# EP3C25.net
KiCad netlist of a schematic drawn in Altium Designer
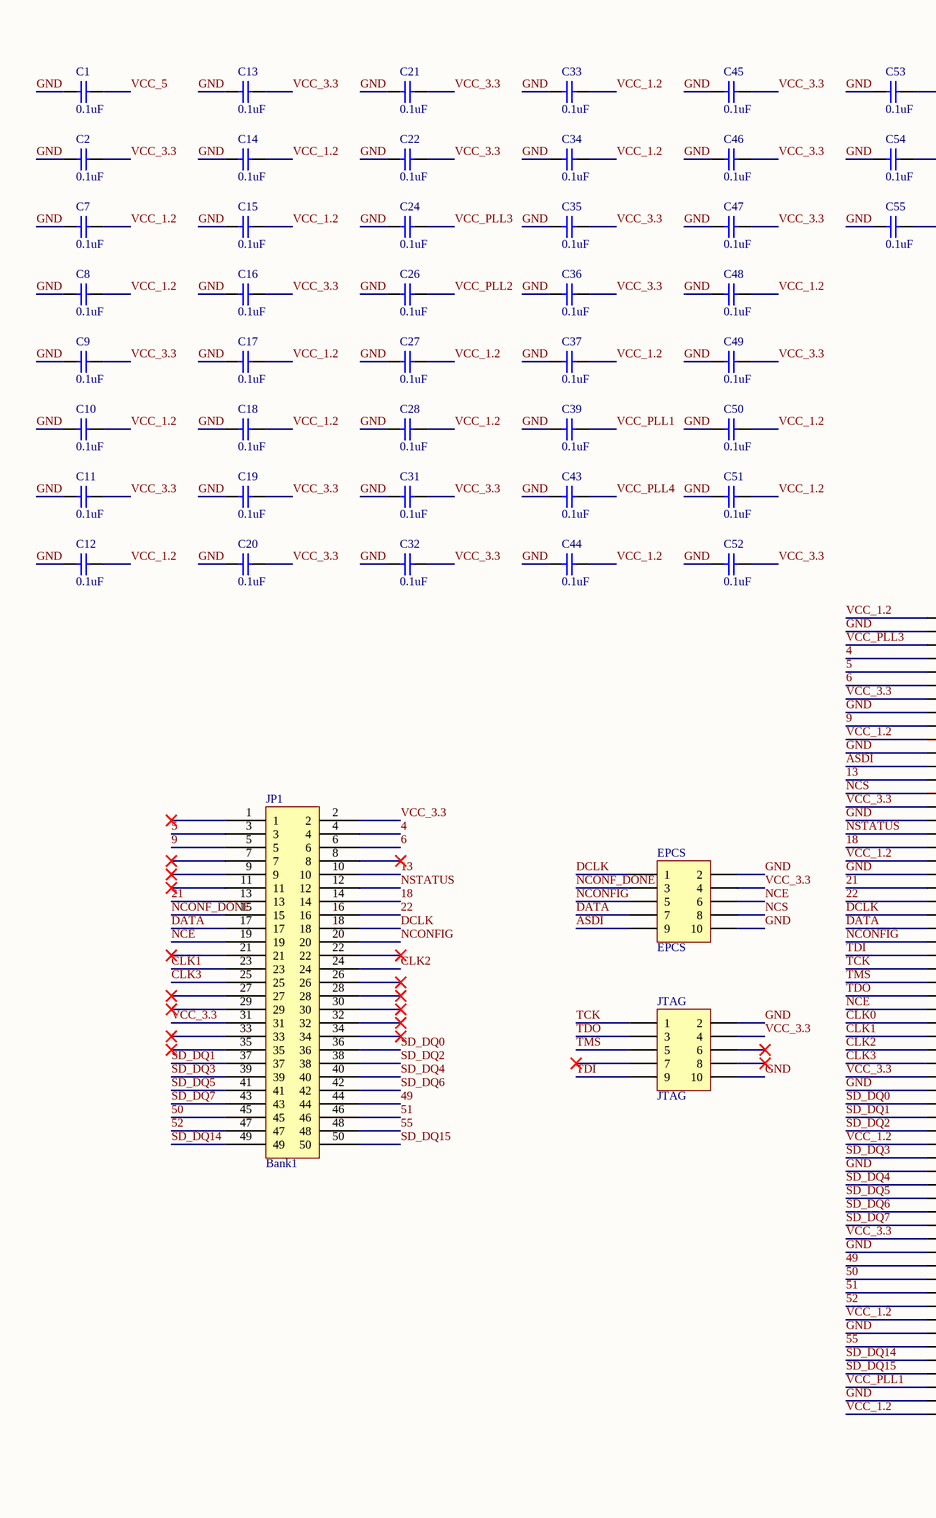
[diagram p0: EP3C25.SchDoc, left]
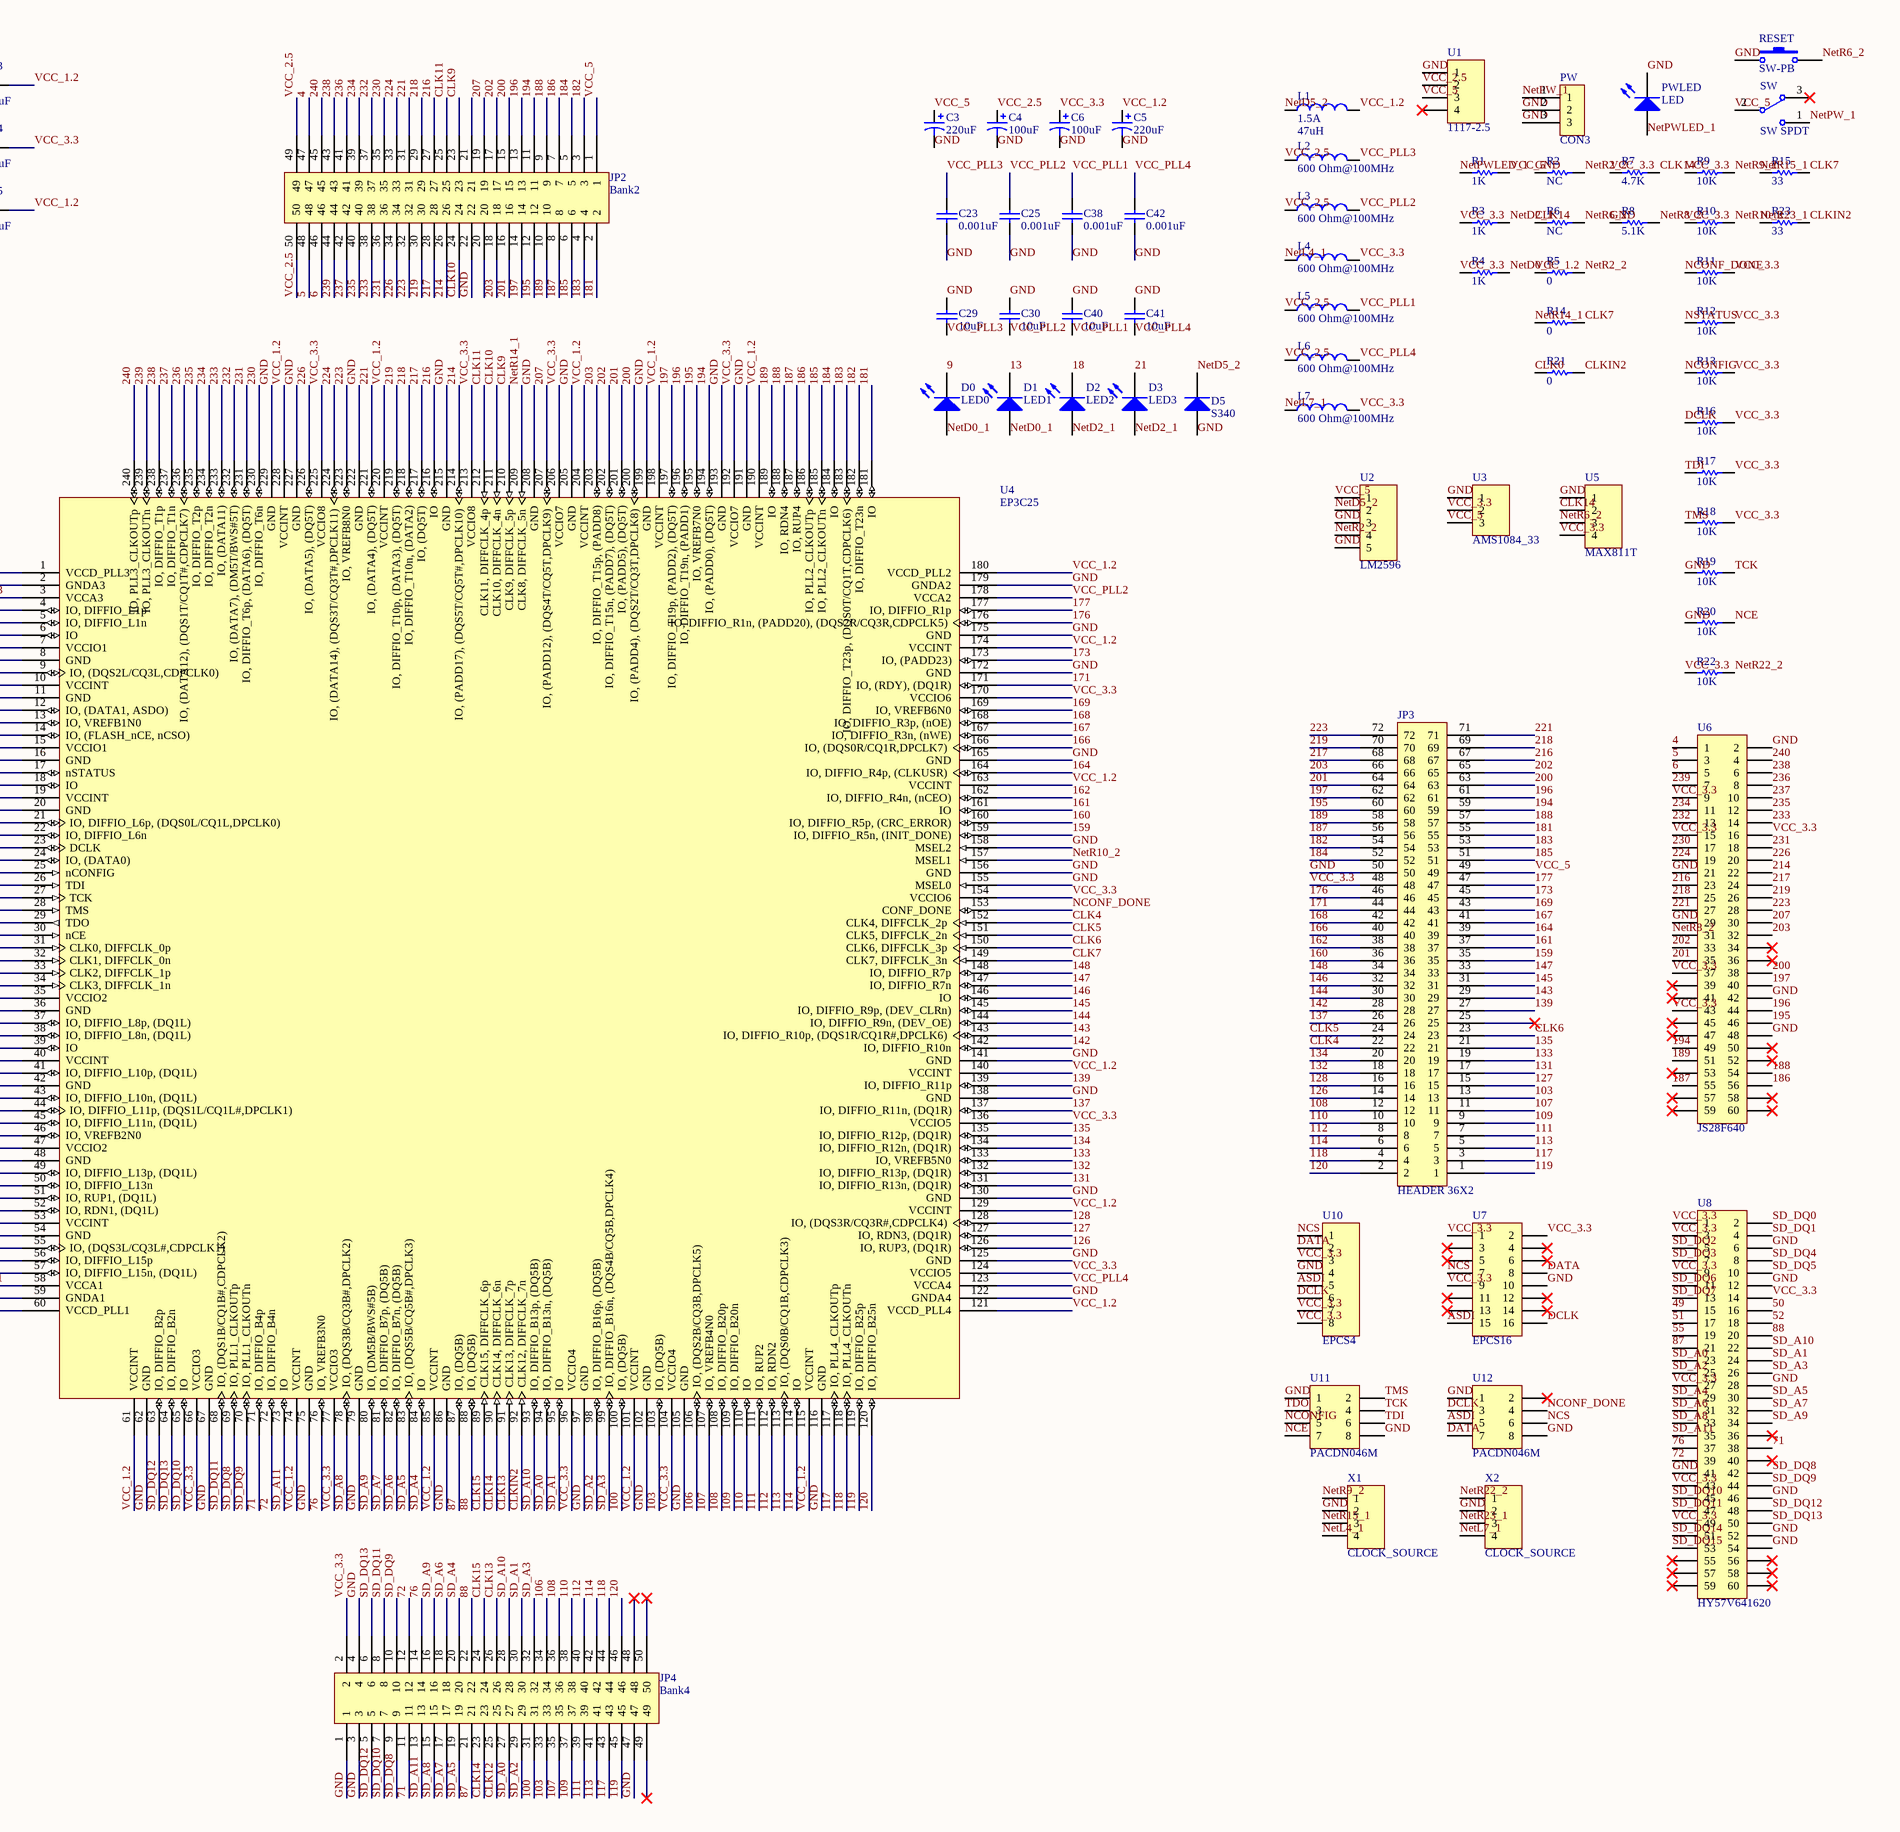
[diagram p1: EP3C25.SchDoc, right]

(export (version "E")
  (design (tool "Eeschema 10.0.6"))
  (components
    (comp (ref "C1")
      (value "0.1uF")
      (footprint "0805C")
      (description "Capacitor")
      (fields (field (name "PUBLISHER") "Altium Limited"))
      (libsource (lib "Miscellaneous Devices") (part "Cap"))
    )
    (comp (ref "C2")
      (value "0.1uF")
      (footprint "0805C")
      (description "Capacitor")
      (fields (field (name "PUBLISHER") "Altium Limited"))
      (libsource (lib "Miscellaneous Devices") (part "Cap"))
    )
    (comp (ref "C3")
      (value "220uF")
      (footprint "Cap6.6*6.6")
      (description "Polarized Capacitor (Radial)")
      (fields (field (name "PUBLISHER") "Altium Limited"))
      (libsource (lib "Miscellaneous Devices") (part "Cap Pol1"))
    )
    (comp (ref "C4")
      (value "100uF")
      (footprint "Cap6.6*6.6")
      (description "Polarized Capacitor (Radial)")
      (fields (field (name "PUBLISHER") "Altium Limited"))
      (libsource (lib "Miscellaneous Devices") (part "Cap Pol1"))
    )
    (comp (ref "C5")
      (value "220uF")
      (footprint "8228")
      (description "Polarized Capacitor (Radial)")
      (fields (field (name "PUBLISHER") "Altium Limited"))
      (libsource (lib "Miscellaneous Devices") (part "Cap Pol1"))
    )
    (comp (ref "C6")
      (value "100uF")
      (footprint "Cap6.6*6.6")
      (description "Polarized Capacitor (Radial)")
      (fields (field (name "PUBLISHER") "Altium Limited"))
      (libsource (lib "Miscellaneous Devices") (part "Cap Pol1"))
    )
    (comp (ref "C7")
      (value "0.1uF")
      (footprint "0805C")
      (description "Capacitor")
      (fields (field (name "PUBLISHER") "Altium Limited"))
      (libsource (lib "Miscellaneous Devices") (part "Cap"))
    )
    (comp (ref "C8")
      (value "0.1uF")
      (footprint "0805C")
      (description "Capacitor")
      (fields (field (name "PUBLISHER") "Altium Limited"))
      (libsource (lib "Miscellaneous Devices") (part "Cap"))
    )
    (comp (ref "C9")
      (value "0.1uF")
      (footprint "0805C")
      (description "Capacitor")
      (fields (field (name "PUBLISHER") "Altium Limited"))
      (libsource (lib "Miscellaneous Devices") (part "Cap"))
    )
    (comp (ref "C10")
      (value "0.1uF")
      (footprint "0805C")
      (description "Capacitor")
      (fields (field (name "PUBLISHER") "Altium Limited"))
      (libsource (lib "Miscellaneous Devices") (part "Cap"))
    )
    (comp (ref "C11")
      (value "0.1uF")
      (footprint "0805C")
      (description "Capacitor")
      (fields (field (name "PUBLISHER") "Altium Limited"))
      (libsource (lib "Miscellaneous Devices") (part "Cap"))
    )
    (comp (ref "C12")
      (value "0.1uF")
      (footprint "0805C")
      (description "Capacitor")
      (fields (field (name "PUBLISHER") "Altium Limited"))
      (libsource (lib "Miscellaneous Devices") (part "Cap"))
    )
    (comp (ref "C13")
      (value "0.1uF")
      (footprint "0805C")
      (description "Capacitor")
      (fields (field (name "PUBLISHER") "Altium Limited"))
      (libsource (lib "Miscellaneous Devices") (part "Cap"))
    )
    (comp (ref "C14")
      (value "0.1uF")
      (footprint "0805C")
      (description "Capacitor")
      (fields (field (name "PUBLISHER") "Altium Limited"))
      (libsource (lib "Miscellaneous Devices") (part "Cap"))
    )
    (comp (ref "C15")
      (value "0.1uF")
      (footprint "0805C")
      (description "Capacitor")
      (fields (field (name "PUBLISHER") "Altium Limited"))
      (libsource (lib "Miscellaneous Devices") (part "Cap"))
    )
    (comp (ref "C16")
      (value "0.1uF")
      (footprint "0805C")
      (description "Capacitor")
      (fields (field (name "PUBLISHER") "Altium Limited"))
      (libsource (lib "Miscellaneous Devices") (part "Cap"))
    )
    (comp (ref "C17")
      (value "0.1uF")
      (footprint "0805C")
      (description "Capacitor")
      (fields (field (name "PUBLISHER") "Altium Limited"))
      (libsource (lib "Miscellaneous Devices") (part "Cap"))
    )
    (comp (ref "C18")
      (value "0.1uF")
      (footprint "0805C")
      (description "Capacitor")
      (fields (field (name "PUBLISHER") "Altium Limited"))
      (libsource (lib "Miscellaneous Devices") (part "Cap"))
    )
    (comp (ref "C19")
      (value "0.1uF")
      (footprint "0805C")
      (description "Capacitor")
      (fields (field (name "PUBLISHER") "Altium Limited"))
      (libsource (lib "Miscellaneous Devices") (part "Cap"))
    )
    (comp (ref "C20")
      (value "0.1uF")
      (footprint "0805C")
      (description "Capacitor")
      (fields (field (name "PUBLISHER") "Altium Limited"))
      (libsource (lib "Miscellaneous Devices") (part "Cap"))
    )
    (comp (ref "C21")
      (value "0.1uF")
      (footprint "0805C")
      (description "Capacitor")
      (fields (field (name "PUBLISHER") "Altium Limited"))
      (libsource (lib "Miscellaneous Devices") (part "Cap"))
    )
    (comp (ref "C22")
      (value "0.1uF")
      (footprint "0805C")
      (description "Capacitor")
      (fields (field (name "PUBLISHER") "Altium Limited"))
      (libsource (lib "Miscellaneous Devices") (part "Cap"))
    )
    (comp (ref "C23")
      (value "0.001uF")
      (footprint "0805C")
      (description "Capacitor")
      (fields (field (name "PUBLISHER") "Altium Limited"))
      (libsource (lib "Miscellaneous Devices") (part "Cap"))
    )
    (comp (ref "C24")
      (value "0.1uF")
      (footprint "0805C")
      (description "Capacitor")
      (fields (field (name "PUBLISHER") "Altium Limited"))
      (libsource (lib "Miscellaneous Devices") (part "Cap"))
    )
    (comp (ref "C25")
      (value "0.001uF")
      (footprint "0805C")
      (description "Capacitor")
      (fields (field (name "PUBLISHER") "Altium Limited"))
      (libsource (lib "Miscellaneous Devices") (part "Cap"))
    )
    (comp (ref "C26")
      (value "0.1uF")
      (footprint "0805C")
      (description "Capacitor")
      (fields (field (name "PUBLISHER") "Altium Limited"))
      (libsource (lib "Miscellaneous Devices") (part "Cap"))
    )
    (comp (ref "C27")
      (value "0.1uF")
      (footprint "0805C")
      (description "Capacitor")
      (fields (field (name "PUBLISHER") "Altium Limited"))
      (libsource (lib "Miscellaneous Devices") (part "Cap"))
    )
    (comp (ref "C28")
      (value "0.1uF")
      (footprint "0805C")
      (description "Capacitor")
      (fields (field (name "PUBLISHER") "Altium Limited"))
      (libsource (lib "Miscellaneous Devices") (part "Cap"))
    )
    (comp (ref "C29")
      (value "10uF")
      (footprint "3216C/A")
      (description "Capacitor")
      (fields (field (name "PUBLISHER") "Altium Limited"))
      (libsource (lib "Miscellaneous Devices") (part "Cap"))
    )
    (comp (ref "C30")
      (value "10uF")
      (footprint "3216C/A")
      (description "Capacitor")
      (fields (field (name "PUBLISHER") "Altium Limited"))
      (libsource (lib "Miscellaneous Devices") (part "Cap"))
    )
    (comp (ref "C31")
      (value "0.1uF")
      (footprint "0805C")
      (description "Capacitor")
      (fields (field (name "PUBLISHER") "Altium Limited"))
      (libsource (lib "Miscellaneous Devices") (part "Cap"))
    )
    (comp (ref "C32")
      (value "0.1uF")
      (footprint "0805C")
      (description "Capacitor")
      (fields (field (name "PUBLISHER") "Altium Limited"))
      (libsource (lib "Miscellaneous Devices") (part "Cap"))
    )
    (comp (ref "C33")
      (value "0.1uF")
      (footprint "0805C")
      (description "Capacitor")
      (fields (field (name "PUBLISHER") "Altium Limited"))
      (libsource (lib "Miscellaneous Devices") (part "Cap"))
    )
    (comp (ref "C34")
      (value "0.1uF")
      (footprint "0805C")
      (description "Capacitor")
      (fields (field (name "PUBLISHER") "Altium Limited"))
      (libsource (lib "Miscellaneous Devices") (part "Cap"))
    )
    (comp (ref "C35")
      (value "0.1uF")
      (footprint "0805C")
      (description "Capacitor")
      (fields (field (name "PUBLISHER") "Altium Limited"))
      (libsource (lib "Miscellaneous Devices") (part "Cap"))
    )
    (comp (ref "C36")
      (value "0.1uF")
      (footprint "0805C")
      (description "Capacitor")
      (fields (field (name "PUBLISHER") "Altium Limited"))
      (libsource (lib "Miscellaneous Devices") (part "Cap"))
    )
    (comp (ref "C37")
      (value "0.1uF")
      (footprint "0805C")
      (description "Capacitor")
      (fields (field (name "PUBLISHER") "Altium Limited"))
      (libsource (lib "Miscellaneous Devices") (part "Cap"))
    )
    (comp (ref "C38")
      (value "0.001uF")
      (footprint "0805C")
      (description "Capacitor")
      (fields (field (name "PUBLISHER") "Altium Limited"))
      (libsource (lib "Miscellaneous Devices") (part "Cap"))
    )
    (comp (ref "C39")
      (value "0.1uF")
      (footprint "0805C")
      (description "Capacitor")
      (fields (field (name "PUBLISHER") "Altium Limited"))
      (libsource (lib "Miscellaneous Devices") (part "Cap"))
    )
    (comp (ref "C40")
      (value "10uF")
      (footprint "3216C/A")
      (description "Capacitor")
      (fields (field (name "PUBLISHER") "Altium Limited"))
      (libsource (lib "Miscellaneous Devices") (part "Cap"))
    )
    (comp (ref "C41")
      (value "10uF")
      (footprint "3216C/A")
      (description "Capacitor")
      (fields (field (name "PUBLISHER") "Altium Limited"))
      (libsource (lib "Miscellaneous Devices") (part "Cap"))
    )
    (comp (ref "C42")
      (value "0.001uF")
      (footprint "0805C")
      (description "Capacitor")
      (fields (field (name "PUBLISHER") "Altium Limited"))
      (libsource (lib "Miscellaneous Devices") (part "Cap"))
    )
    (comp (ref "C43")
      (value "0.1uF")
      (footprint "0805C")
      (description "Capacitor")
      (fields (field (name "PUBLISHER") "Altium Limited"))
      (libsource (lib "Miscellaneous Devices") (part "Cap"))
    )
    (comp (ref "C44")
      (value "0.1uF")
      (footprint "0805C")
      (description "Capacitor")
      (fields (field (name "PUBLISHER") "Altium Limited"))
      (libsource (lib "Miscellaneous Devices") (part "Cap"))
    )
    (comp (ref "C45")
      (value "0.1uF")
      (footprint "0805C")
      (description "Capacitor")
      (fields (field (name "PUBLISHER") "Altium Limited"))
      (libsource (lib "Miscellaneous Devices") (part "Cap"))
    )
    (comp (ref "C46")
      (value "0.1uF")
      (footprint "0805C")
      (description "Capacitor")
      (fields (field (name "PUBLISHER") "Altium Limited"))
      (libsource (lib "Miscellaneous Devices") (part "Cap"))
    )
    (comp (ref "C47")
      (value "0.1uF")
      (footprint "0805C")
      (description "Capacitor")
      (fields (field (name "PUBLISHER") "Altium Limited"))
      (libsource (lib "Miscellaneous Devices") (part "Cap"))
    )
    (comp (ref "C48")
      (value "0.1uF")
      (footprint "0805C")
      (description "Capacitor")
      (fields (field (name "PUBLISHER") "Altium Limited"))
      (libsource (lib "Miscellaneous Devices") (part "Cap"))
    )
    (comp (ref "C49")
      (value "0.1uF")
      (footprint "0805C")
      (description "Capacitor")
      (fields (field (name "PUBLISHER") "Altium Limited"))
      (libsource (lib "Miscellaneous Devices") (part "Cap"))
    )
    (comp (ref "C50")
      (value "0.1uF")
      (footprint "0805C")
      (description "Capacitor")
      (fields (field (name "PUBLISHER") "Altium Limited"))
      (libsource (lib "Miscellaneous Devices") (part "Cap"))
    )
    (comp (ref "C51")
      (value "0.1uF")
      (footprint "0805C")
      (description "Capacitor")
      (fields (field (name "PUBLISHER") "Altium Limited"))
      (libsource (lib "Miscellaneous Devices") (part "Cap"))
    )
    (comp (ref "C52")
      (value "0.1uF")
      (footprint "0805C")
      (description "Capacitor")
      (fields (field (name "PUBLISHER") "Altium Limited"))
      (libsource (lib "Miscellaneous Devices") (part "Cap"))
    )
    (comp (ref "C53")
      (value "0.1uF")
      (footprint "0805C")
      (description "Capacitor")
      (fields (field (name "PUBLISHER") "Altium Limited"))
      (libsource (lib "Miscellaneous Devices") (part "Cap"))
    )
    (comp (ref "C54")
      (value "0.1uF")
      (footprint "0805C")
      (description "Capacitor")
      (fields (field (name "PUBLISHER") "Altium Limited"))
      (libsource (lib "Miscellaneous Devices") (part "Cap"))
    )
    (comp (ref "C55")
      (value "0.1uF")
      (footprint "0805C")
      (description "Capacitor")
      (fields (field (name "PUBLISHER") "Altium Limited"))
      (libsource (lib "Miscellaneous Devices") (part "Cap"))
    )
    (comp (ref "D0")
      (value "LED0")
      (footprint "0805A")
      (description "Typical INFRARED GaAs LED")
      (fields (field (name "PUBLISHER") "Altium Limited"))
      (libsource (lib "Miscellaneous Devices") (part "LED0"))
    )
    (comp (ref "D1")
      (value "LED1")
      (footprint "0805A")
      (description "Typical INFRARED GaAs LED")
      (fields (field (name "PUBLISHER") "Altium Limited"))
      (libsource (lib "Miscellaneous Devices") (part "LED0"))
    )
    (comp (ref "D2")
      (value "LED2")
      (footprint "0805A")
      (description "Typical INFRARED GaAs LED")
      (fields (field (name "PUBLISHER") "Altium Limited"))
      (libsource (lib "Miscellaneous Devices") (part "LED0"))
    )
    (comp (ref "D3")
      (value "LED3")
      (footprint "0805A")
      (description "Typical INFRARED GaAs LED")
      (fields (field (name "PUBLISHER") "Altium Limited"))
      (libsource (lib "Miscellaneous Devices") (part "LED0"))
    )
    (comp (ref "D5")
      (value "S340")
      (footprint "SMB")
      (description "Default Diode")
      (fields (field (name "PUBLISHER") "Altium Limited"))
      (libsource (lib "Miscellaneous Devices") (part "Diode"))
    )
    (comp (ref "EPCS")
      (value "EPCS")
      (footprint "IDC10_S")
      (description "Header, 5-Pin, Dual row")
      (fields (field (name "PUBLISHER") "Altium Limited"))
      (libsource (lib "Miscellaneous Connectors") (part "Header 5X2"))
    )
    (comp (ref "JP1")
      (value "Bank1")
      (footprint "IDC50-S")
      (libsource (lib "EP3C25") (part "CORE_CONNECTOR_LEFT"))
    )
    (comp (ref "JP2")
      (value "Bank2")
      (footprint "IDC50-S")
      (libsource (lib "EP3C25") (part "CORE_CONNECTOR_FRONT"))
    )
    (comp (ref "JP3")
      (value "HEADER 36X2")
      (footprint "IDC72_S")
      (libsource (lib "EP3C25") (part "CORE_CONNECTOR_RIGHT"))
    )
    (comp (ref "JP4")
      (value "Bank4")
      (footprint "IDC50-S")
      (libsource (lib "EP3C25") (part "CORE_CONNECTOR_BACK"))
    )
    (comp (ref "JTAG")
      (value "JTAG")
      (footprint "IDC10_S")
      (description "Header, 5-Pin, Dual row")
      (fields (field (name "PUBLISHER") "Altium Limited"))
      (libsource (lib "Miscellaneous Connectors") (part "Header 5X2"))
    )
    (comp (ref "L1")
      (value "1.5A")
      (footprint "临时画的电感封装")
      (description "Inductor")
      (fields (field (name "ALTIUM_VALUE") "47uH") (field (name "PUBLISHER") "Altium Limited"))
      (libsource (lib "Miscellaneous Devices") (part "Inductor"))
    )
    (comp (ref "L2")
      (value "600 Ohm@100MHz")
      (footprint "0805R")
      (description "Inductor")
      (fields (field (name "PUBLISHER") "Altium Limited"))
      (libsource (lib "Miscellaneous Devices") (part "Inductor"))
    )
    (comp (ref "L3")
      (value "600 Ohm@100MHz")
      (footprint "0805R")
      (description "Inductor")
      (fields (field (name "PUBLISHER") "Altium Limited"))
      (libsource (lib "Miscellaneous Devices") (part "Inductor"))
    )
    (comp (ref "L4")
      (value "600 Ohm@100MHz")
      (footprint "0805R")
      (description "Inductor")
      (fields (field (name "PUBLISHER") "Altium Limited"))
      (libsource (lib "Miscellaneous Devices") (part "Inductor"))
    )
    (comp (ref "L5")
      (value "600 Ohm@100MHz")
      (footprint "0805R")
      (description "Inductor")
      (fields (field (name "PUBLISHER") "Altium Limited"))
      (libsource (lib "Miscellaneous Devices") (part "Inductor"))
    )
    (comp (ref "L6")
      (value "600 Ohm@100MHz")
      (footprint "0805R")
      (description "Inductor")
      (fields (field (name "PUBLISHER") "Altium Limited"))
      (libsource (lib "Miscellaneous Devices") (part "Inductor"))
    )
    (comp (ref "L7")
      (value "600 Ohm@100MHz")
      (footprint "0805R")
      (description "Inductor")
      (fields (field (name "PUBLISHER") "Altium Limited"))
      (libsource (lib "Miscellaneous Devices") (part "Inductor"))
    )
    (comp (ref "PW") (value "CON3") (footprint "PW_PORT") (libsource (lib "EP3C25") (part "CON3")))
    (comp (ref "PWLED")
      (value "LED")
      (footprint "0805A")
      (description "Typical INFRARED GaAs LED")
      (fields (field (name "PUBLISHER") "Altium Limited"))
      (libsource (lib "Miscellaneous Devices") (part "LED0"))
    )
    (comp (ref "R1")
      (value "1K")
      (footprint "0805R")
      (description "Resistor")
      (fields (field (name "PUBLISHER") "Altium Limited"))
      (libsource (lib "Miscellaneous Devices") (part "Res1"))
    )
    (comp (ref "R2")
      (value "NC")
      (footprint "0805R")
      (description "Resistor")
      (fields (field (name "PUBLISHER") "Altium Limited"))
      (libsource (lib "Miscellaneous Devices") (part "Res1"))
    )
    (comp (ref "R3")
      (value "1K")
      (footprint "0805R")
      (description "Resistor")
      (fields (field (name "PUBLISHER") "Altium Limited"))
      (libsource (lib "Miscellaneous Devices") (part "Res1"))
    )
    (comp (ref "R4")
      (value "1K")
      (footprint "0805R")
      (description "Resistor")
      (fields (field (name "PUBLISHER") "Altium Limited"))
      (libsource (lib "Miscellaneous Devices") (part "Res1"))
    )
    (comp (ref "R5")
      (value "0")
      (footprint "0805R")
      (description "Resistor")
      (fields (field (name "PUBLISHER") "Altium Limited"))
      (libsource (lib "Miscellaneous Devices") (part "Res1"))
    )
    (comp (ref "R6")
      (value "NC")
      (footprint "0805R")
      (description "Resistor")
      (fields (field (name "PUBLISHER") "Altium Limited"))
      (libsource (lib "Miscellaneous Devices") (part "Res1"))
    )
    (comp (ref "R7")
      (value "4.7K")
      (footprint "0805R")
      (description "Resistor")
      (fields (field (name "PUBLISHER") "Altium Limited"))
      (libsource (lib "Miscellaneous Devices") (part "Res1"))
    )
    (comp (ref "R8")
      (value "5.1K")
      (footprint "0805R")
      (description "Resistor")
      (fields (field (name "PUBLISHER") "Altium Limited"))
      (libsource (lib "Miscellaneous Devices") (part "Res1"))
    )
    (comp (ref "R9")
      (value "10K")
      (footprint "0805R")
      (description "Resistor")
      (fields (field (name "PUBLISHER") "Altium Limited"))
      (libsource (lib "Miscellaneous Devices") (part "Res1"))
    )
    (comp (ref "R10")
      (value "10K")
      (footprint "0805R")
      (description "Resistor")
      (fields (field (name "PUBLISHER") "Altium Limited"))
      (libsource (lib "Miscellaneous Devices") (part "Res1"))
    )
    (comp (ref "R11")
      (value "10K")
      (footprint "0805R")
      (description "Resistor")
      (fields (field (name "PUBLISHER") "Altium Limited"))
      (libsource (lib "Miscellaneous Devices") (part "Res1"))
    )
    (comp (ref "R12")
      (value "10K")
      (footprint "0805R")
      (description "Resistor")
      (fields (field (name "PUBLISHER") "Altium Limited"))
      (libsource (lib "Miscellaneous Devices") (part "Res1"))
    )
    (comp (ref "R13")
      (value "10K")
      (footprint "0805R")
      (description "Resistor")
      (fields (field (name "PUBLISHER") "Altium Limited"))
      (libsource (lib "Miscellaneous Devices") (part "Res1"))
    )
    (comp (ref "R14")
      (value "0")
      (footprint "0805R")
      (description "Resistor")
      (fields (field (name "PUBLISHER") "Altium Limited"))
      (libsource (lib "Miscellaneous Devices") (part "Res1"))
    )
    (comp (ref "R15")
      (value "33")
      (footprint "0805R")
      (description "Resistor")
      (fields (field (name "PUBLISHER") "Altium Limited"))
      (libsource (lib "Miscellaneous Devices") (part "Res1"))
    )
    (comp (ref "R16")
      (value "10K")
      (footprint "0805R")
      (description "Resistor")
      (fields (field (name "PUBLISHER") "Altium Limited"))
      (libsource (lib "Miscellaneous Devices") (part "Res1"))
    )
    (comp (ref "R17")
      (value "10K")
      (footprint "0805R")
      (description "Resistor")
      (fields (field (name "PUBLISHER") "Altium Limited"))
      (libsource (lib "Miscellaneous Devices") (part "Res1"))
    )
    (comp (ref "R18")
      (value "10K")
      (footprint "0805R")
      (description "Resistor")
      (fields (field (name "PUBLISHER") "Altium Limited"))
      (libsource (lib "Miscellaneous Devices") (part "Res1"))
    )
    (comp (ref "R19")
      (value "10K")
      (footprint "0805R")
      (description "Resistor")
      (fields (field (name "PUBLISHER") "Altium Limited"))
      (libsource (lib "Miscellaneous Devices") (part "Res1"))
    )
    (comp (ref "R20")
      (value "10K")
      (footprint "0805R")
      (description "Resistor")
      (fields (field (name "PUBLISHER") "Altium Limited"))
      (libsource (lib "Miscellaneous Devices") (part "Res1"))
    )
    (comp (ref "R21")
      (value "0")
      (footprint "0805R")
      (description "Resistor")
      (fields (field (name "PUBLISHER") "Altium Limited"))
      (libsource (lib "Miscellaneous Devices") (part "Res1"))
    )
    (comp (ref "R22")
      (value "10K")
      (footprint "0805R")
      (description "Resistor")
      (fields (field (name "PUBLISHER") "Altium Limited"))
      (libsource (lib "Miscellaneous Devices") (part "Res1"))
    )
    (comp (ref "R23")
      (value "33")
      (footprint "0805R")
      (description "Resistor")
      (fields (field (name "PUBLISHER") "Altium Limited"))
      (libsource (lib "Miscellaneous Devices") (part "Res1"))
    )
    (comp (ref "RESET")
      (value "SW-PB")
      (footprint "SMD_SWITH")
      (description "Switch")
      (fields (field (name "PUBLISHER") "Altium Limited"))
      (libsource (lib "Miscellaneous Devices") (part "SW-PB"))
    )
    (comp (ref "SW")
      (value "SW SPDT")
      (footprint "PW_SW")
      (description "SPDT Subminiature Toggle Switch, Right Angle Mounting, Vertical Actuation")
      (fields (field (name "PUBLISHER") "Altium Limited"))
      (libsource (lib "Miscellaneous Devices") (part "SW-SPDT"))
    )
    (comp (ref "U1")
      (value "1117-2.5")
      (footprint "SOT-223")
      (description "Header, 4-Pin")
      (fields (field (name "PUBLISHER") "Altium Limited"))
      (libsource (lib "Miscellaneous Connectors") (part "Header 4"))
    )
    (comp (ref "U2")
      (value "LM2596")
      (footprint "LM2596_TO263")
      (description "Header, 5-Pin")
      (fields (field (name "PUBLISHER") "Altium Limited"))
      (libsource (lib "Miscellaneous Connectors") (part "Header 5"))
    )
    (comp (ref "U3")
      (value "AMS1084_33")
      (footprint "AMS1084-ADJ")
      (description "Header, 3-Pin")
      (fields (field (name "PUBLISHER") "Altium Limited"))
      (libsource (lib "Miscellaneous Connectors") (part "Header 3"))
    )
    (comp (ref "U4") (value "EP3C25") (footprint "PQFP240") (libsource (lib "EP3C25") (part "EP3C25Q240C8")))
    (comp (ref "U5")
      (value "MAX811T")
      (footprint "SOT143")
      (description "Header, 4-Pin")
      (fields (field (name "PUBLISHER") "Altium Limited"))
      (libsource (lib "Miscellaneous Connectors") (part "Header 4"))
    )
    (comp (ref "U6")
      (value "JS28F640")
      (footprint "SOP56_E28F640")
      (description "Header, 30-Pin, Dual row")
      (fields (field (name "PUBLISHER") "Altium Limited"))
      (libsource (lib "Miscellaneous Connectors") (part "Header 30X2"))
    )
    (comp (ref "U7")
      (value "EPCS16")
      (footprint "SOP16_EPCS16")
      (description "Header, 8-Pin, Dual row")
      (fields (field (name "PUBLISHER") "Altium Limited"))
      (libsource (lib "Miscellaneous Connectors") (part "Header 8X2"))
    )
    (comp (ref "U8")
      (value "HY57V641620")
      (footprint "TSOP54")
      (description "Header, 30-Pin, Dual row")
      (fields (field (name "PUBLISHER") "Altium Limited"))
      (libsource (lib "Miscellaneous Connectors") (part "Header 30X2"))
    )
    (comp (ref "U10")
      (value "EPCS4")
      (footprint "so8")
      (description "Header, 8-Pin")
      (fields (field (name "PUBLISHER") "Altium Limited"))
      (libsource (lib "Miscellaneous Connectors") (part "Header 8"))
    )
    (comp (ref "U11")
      (value "PACDN046M")
      (footprint "MSOP8")
      (description "Header, 4-Pin, Dual row")
      (fields (field (name "PUBLISHER") "Altium Limited"))
      (libsource (lib "Miscellaneous Connectors") (part "Header 4X2"))
    )
    (comp (ref "U12")
      (value "PACDN046M")
      (footprint "MSOP8")
      (description "Header, 4-Pin, Dual row")
      (fields (field (name "PUBLISHER") "Altium Limited"))
      (libsource (lib "Miscellaneous Connectors") (part "Header 4X2"))
    )
    (comp (ref "X1")
      (value "CLOCK_SOURCE")
      (footprint "CRYSTAL4")
      (description "Header, 4-Pin")
      (fields (field (name "PUBLISHER") "Altium Limited"))
      (libsource (lib "Miscellaneous Connectors") (part "Header 4"))
    )
    (comp (ref "X2")
      (value "CLOCK_SOURCE")
      (footprint "CRYSTAL4")
      (description "Header, 4-Pin")
      (fields (field (name "PUBLISHER") "Altium Limited"))
      (libsource (lib "Miscellaneous Connectors") (part "Header 4"))
    )
  )
  (nets
    (net (code "1") (name "/4") (class "Default")
      (node (ref "JP1") (pin "4") (pinfunction "4_4") (pintype "passive"))
      (node (ref "JP2") (pin "47") (pinfunction "47_47") (pintype "passive"))
      (node (ref "U4") (pin "4") (pinfunction "IO,_DIFFIO_L1p_4") (pintype "bidirectional"))
      (node (ref "U6") (pin "1") (pinfunction "1_1") (pintype "passive"))
    )
    (net (code "2") (name "/5") (class "Default")
      (node (ref "JP1") (pin "3") (pinfunction "3_3") (pintype "passive"))
      (node (ref "JP2") (pin "48") (pinfunction "48_48") (pintype "passive"))
      (node (ref "U4") (pin "5") (pinfunction "IO,_DIFFIO_L1n_5") (pintype "bidirectional"))
      (node (ref "U6") (pin "3") (pinfunction "3_3") (pintype "passive"))
    )
    (net (code "3") (name "/6") (class "Default")
      (node (ref "JP1") (pin "6") (pinfunction "6_6") (pintype "passive"))
      (node (ref "JP2") (pin "46") (pinfunction "46_46") (pintype "passive"))
      (node (ref "U4") (pin "6") (pinfunction "IO_6") (pintype "bidirectional"))
      (node (ref "U6") (pin "5") (pinfunction "5_5") (pintype "passive"))
    )
    (net (code "4") (name "/9") (class "Default")
      (node (ref "D0") (pin "2") (pinfunction "K_2") (pintype "passive"))
      (node (ref "JP1") (pin "5") (pinfunction "5_5") (pintype "passive"))
      (node (ref "U4") (pin "9") (pinfunction "IO,_(DQS2L/CQ3L,CDPCLK0)_9") (pintype "bidirectional"))
    )
    (net (code "5") (name "/13") (class "Default")
      (node (ref "D1") (pin "2") (pinfunction "K_2") (pintype "passive"))
      (node (ref "JP1") (pin "10") (pinfunction "10_10") (pintype "passive"))
      (node (ref "U4") (pin "13") (pinfunction "IO,_VREFB1N0_13") (pintype "bidirectional"))
    )
    (net (code "6") (name "/18") (class "Default")
      (node (ref "D2") (pin "2") (pinfunction "K_2") (pintype "passive"))
      (node (ref "JP1") (pin "14") (pinfunction "14_14") (pintype "passive"))
      (node (ref "U4") (pin "18") (pinfunction "IO_18") (pintype "bidirectional"))
    )
    (net (code "7") (name "/21") (class "Default")
      (node (ref "D3") (pin "2") (pinfunction "K_2") (pintype "passive"))
      (node (ref "JP1") (pin "13") (pinfunction "13_13") (pintype "passive"))
      (node (ref "U4") (pin "21") (pinfunction "IO,_DIFFIO_L6p,_(DQS0L/CQ1L,DPCLK0)_21") (pintype "bidirectional"))
    )
    (net (code "8") (name "/22") (class "Default")
      (node (ref "JP1") (pin "16") (pinfunction "16_16") (pintype "passive"))
      (node (ref "U4") (pin "22") (pinfunction "IO,_DIFFIO_L6n_22") (pintype "bidirectional"))
    )
    (net (code "9") (name "/49") (class "Default")
      (node (ref "JP1") (pin "44") (pinfunction "44_44") (pintype "passive"))
      (node (ref "U4") (pin "49") (pinfunction "IO,_DIFFIO_L13p,_(DQ1L)_49") (pintype "bidirectional"))
      (node (ref "U8") (pin "15") (pinfunction "15_15") (pintype "passive"))
    )
    (net (code "10") (name "/50") (class "Default")
      (node (ref "JP1") (pin "45") (pinfunction "45_45") (pintype "passive"))
      (node (ref "U4") (pin "50") (pinfunction "IO,_DIFFIO_L13n_50") (pintype "bidirectional"))
      (node (ref "U8") (pin "16") (pinfunction "16_16") (pintype "passive"))
    )
    (net (code "11") (name "/51") (class "Default")
      (node (ref "JP1") (pin "46") (pinfunction "46_46") (pintype "passive"))
      (node (ref "U4") (pin "51") (pinfunction "IO,_RUP1,_(DQ1L)_51") (pintype "bidirectional"))
      (node (ref "U8") (pin "17") (pinfunction "17_17") (pintype "passive"))
    )
    (net (code "12") (name "/52") (class "Default")
      (node (ref "JP1") (pin "47") (pinfunction "47_47") (pintype "passive"))
      (node (ref "U4") (pin "52") (pinfunction "IO,_RDN1,_(DQ1L)_52") (pintype "bidirectional"))
      (node (ref "U8") (pin "18") (pinfunction "18_18") (pintype "passive"))
    )
    (net (code "13") (name "/55") (class "Default")
      (node (ref "JP1") (pin "48") (pinfunction "48_48") (pintype "passive"))
      (node (ref "U4") (pin "55") (pinfunction "IO,_(DQS3L/CQ3L#,CDPCLK1)_55") (pintype "bidirectional"))
      (node (ref "U8") (pin "19") (pinfunction "19_19") (pintype "passive"))
    )
    (net (code "14") (name "/71") (class "Default")
      (node (ref "JP4") (pin "11") (pinfunction "11_11") (pintype "passive"))
      (node (ref "U4") (pin "71") (pinfunction "IO,_DIFFIO_B4p_71") (pintype "bidirectional"))
      (node (ref "U8") (pin "38") (pinfunction "38_38") (pintype "passive"))
    )
    (net (code "15") (name "/72") (class "Default")
      (node (ref "JP4") (pin "12") (pinfunction "12_12") (pintype "passive"))
      (node (ref "U4") (pin "72") (pinfunction "IO,_DIFFIO_B4n_72") (pintype "bidirectional"))
      (node (ref "U8") (pin "39") (pinfunction "39_39") (pintype "passive"))
    )
    (net (code "16") (name "/76") (class "Default")
      (node (ref "JP4") (pin "14") (pinfunction "14_14") (pintype "passive"))
      (node (ref "U4") (pin "76") (pinfunction "IO,_VREFB3N0_76") (pintype "bidirectional"))
      (node (ref "U8") (pin "37") (pinfunction "37_37") (pintype "passive"))
    )
    (net (code "17") (name "/87") (class "Default")
      (node (ref "JP4") (pin "21") (pinfunction "21_21") (pintype "passive"))
      (node (ref "U4") (pin "87") (pinfunction "IO,_(DQ5B)_87") (pintype "bidirectional"))
      (node (ref "U8") (pin "21") (pinfunction "21_21") (pintype "passive"))
    )
    (net (code "18") (name "/88") (class "Default")
      (node (ref "JP4") (pin "22") (pinfunction "22_22") (pintype "passive"))
      (node (ref "U4") (pin "88") (pinfunction "IO,_(DQ5B)_88") (pintype "bidirectional"))
      (node (ref "U8") (pin "20") (pinfunction "20_20") (pintype "passive"))
    )
    (net (code "19") (name "/100") (class "Default")
      (node (ref "JP4") (pin "31") (pinfunction "31_31") (pintype "passive"))
      (node (ref "U4") (pin "100") (pinfunction "IO,_(DQ5B)_100") (pintype "bidirectional"))
    )
    (net (code "20") (name "/103") (class "Default")
      (node (ref "JP3") (pin "13") (pinfunction "13_13") (pintype "passive"))
      (node (ref "JP4") (pin "33") (pinfunction "33_33") (pintype "passive"))
      (node (ref "U4") (pin "103") (pinfunction "IO,_(DQ5B)_103") (pintype "bidirectional"))
    )
    (net (code "21") (name "/106") (class "Default")
      (node (ref "JP4") (pin "34") (pinfunction "34_34") (pintype "passive"))
      (node (ref "U4") (pin "106") (pinfunction "IO,_(DQS2B/CQ3B,DPCLK5)_106") (pintype "bidirectional"))
    )
    (net (code "22") (name "/107") (class "Default")
      (node (ref "JP3") (pin "11") (pinfunction "11_11") (pintype "passive"))
      (node (ref "JP4") (pin "35") (pinfunction "35_35") (pintype "passive"))
      (node (ref "U4") (pin "107") (pinfunction "IO,_VREFB4N0_107") (pintype "bidirectional"))
    )
    (net (code "23") (name "/108") (class "Default")
      (node (ref "JP3") (pin "12") (pinfunction "12_12") (pintype "passive"))
      (node (ref "JP4") (pin "36") (pinfunction "36_36") (pintype "passive"))
      (node (ref "U4") (pin "108") (pinfunction "IO,_DIFFIO_B20p_108") (pintype "bidirectional"))
    )
    (net (code "24") (name "/109") (class "Default")
      (node (ref "JP3") (pin "9") (pinfunction "9_9") (pintype "passive"))
      (node (ref "JP4") (pin "37") (pinfunction "37_37") (pintype "passive"))
      (node (ref "U4") (pin "109") (pinfunction "IO,_DIFFIO_B20n_109") (pintype "bidirectional"))
    )
    (net (code "25") (name "/110") (class "Default")
      (node (ref "JP3") (pin "10") (pinfunction "10_10") (pintype "passive"))
      (node (ref "JP4") (pin "38") (pinfunction "38_38") (pintype "passive"))
      (node (ref "U4") (pin "110") (pinfunction "IO_110") (pintype "bidirectional"))
    )
    (net (code "26") (name "/111") (class "Default")
      (node (ref "JP3") (pin "7") (pinfunction "7_7") (pintype "passive"))
      (node (ref "JP4") (pin "39") (pinfunction "39_39") (pintype "passive"))
      (node (ref "U4") (pin "111") (pinfunction "IO,_RUP2_111") (pintype "bidirectional"))
    )
    (net (code "27") (name "/112") (class "Default")
      (node (ref "JP3") (pin "8") (pinfunction "8_8") (pintype "passive"))
      (node (ref "JP4") (pin "40") (pinfunction "40_40") (pintype "passive"))
      (node (ref "U4") (pin "112") (pinfunction "IO,_RDN2_112") (pintype "bidirectional"))
    )
    (net (code "28") (name "/113") (class "Default")
      (node (ref "JP3") (pin "5") (pinfunction "5_5") (pintype "passive"))
      (node (ref "JP4") (pin "41") (pinfunction "41_41") (pintype "passive"))
      (node (ref "U4") (pin "113") (pinfunction "IO,_(DQS0B/CQ1B,CDPCLK3)_113") (pintype "bidirectional"))
    )
    (net (code "29") (name "/114") (class "Default")
      (node (ref "JP3") (pin "6") (pinfunction "6_6") (pintype "passive"))
      (node (ref "JP4") (pin "42") (pinfunction "42_42") (pintype "passive"))
      (node (ref "U4") (pin "114") (pinfunction "IO_114") (pintype "bidirectional"))
    )
    (net (code "30") (name "/117") (class "Default")
      (node (ref "JP3") (pin "3") (pinfunction "3_3") (pintype "passive"))
      (node (ref "JP4") (pin "43") (pinfunction "43_43") (pintype "passive"))
      (node (ref "U4") (pin "117") (pinfunction "IO,_PLL4_CLKOUTp_117") (pintype "bidirectional"))
    )
    (net (code "31") (name "/118") (class "Default")
      (node (ref "JP3") (pin "4") (pinfunction "4_4") (pintype "passive"))
      (node (ref "JP4") (pin "44") (pinfunction "44_44") (pintype "passive"))
      (node (ref "U4") (pin "118") (pinfunction "IO,_PLL4_CLKOUTn_118") (pintype "bidirectional"))
    )
    (net (code "32") (name "/119") (class "Default")
      (node (ref "JP3") (pin "1") (pinfunction "1_1") (pintype "passive"))
      (node (ref "JP4") (pin "45") (pinfunction "45_45") (pintype "passive"))
      (node (ref "U4") (pin "119") (pinfunction "IO,_DIFFIO_B25p_119") (pintype "bidirectional"))
    )
    (net (code "33") (name "/120") (class "Default")
      (node (ref "JP3") (pin "2") (pinfunction "2_2") (pintype "passive"))
      (node (ref "JP4") (pin "46") (pinfunction "46_46") (pintype "passive"))
      (node (ref "U4") (pin "120") (pinfunction "IO,_DIFFIO_B25n_120") (pintype "bidirectional"))
    )
    (net (code "34") (name "/126") (class "Default")
      (node (ref "JP3") (pin "14") (pinfunction "14_14") (pintype "passive"))
      (node (ref "U4") (pin "126") (pinfunction "IO,_RUP3,_(DQ1R)_126") (pintype "bidirectional"))
    )
    (net (code "35") (name "/127") (class "Default")
      (node (ref "JP3") (pin "15") (pinfunction "15_15") (pintype "passive"))
      (node (ref "U4") (pin "127") (pinfunction "IO,_RDN3,_(DQ1R)_127") (pintype "bidirectional"))
    )
    (net (code "36") (name "/128") (class "Default")
      (node (ref "JP3") (pin "16") (pinfunction "16_16") (pintype "passive"))
      (node (ref "U4") (pin "128") (pinfunction "IO,_(DQS3R/CQ3R#,CDPCLK4)_128") (pintype "bidirectional"))
    )
    (net (code "37") (name "/131") (class "Default")
      (node (ref "JP3") (pin "17") (pinfunction "17_17") (pintype "passive"))
      (node (ref "U4") (pin "131") (pinfunction "IO,_DIFFIO_R13n,_(DQ1R)_131") (pintype "bidirectional"))
    )
    (net (code "38") (name "/132") (class "Default")
      (node (ref "JP3") (pin "18") (pinfunction "18_18") (pintype "passive"))
      (node (ref "U4") (pin "132") (pinfunction "IO,_DIFFIO_R13p,_(DQ1R)_132") (pintype "bidirectional"))
    )
    (net (code "39") (name "/133") (class "Default")
      (node (ref "JP3") (pin "19") (pinfunction "19_19") (pintype "passive"))
      (node (ref "U4") (pin "133") (pinfunction "IO,_VREFB5N0_133") (pintype "bidirectional"))
    )
    (net (code "40") (name "/134") (class "Default")
      (node (ref "JP3") (pin "20") (pinfunction "20_20") (pintype "passive"))
      (node (ref "U4") (pin "134") (pinfunction "IO,_DIFFIO_R12n,_(DQ1R)_134") (pintype "bidirectional"))
    )
    (net (code "41") (name "/135") (class "Default")
      (node (ref "JP3") (pin "21") (pinfunction "21_21") (pintype "passive"))
      (node (ref "U4") (pin "135") (pinfunction "IO,_DIFFIO_R12p,_(DQ1R)_135") (pintype "bidirectional"))
    )
    (net (code "42") (name "/137") (class "Default")
      (node (ref "JP3") (pin "26") (pinfunction "26_26") (pintype "passive"))
      (node (ref "U4") (pin "137") (pinfunction "IO,_DIFFIO_R11n,_(DQ1R)_137") (pintype "bidirectional"))
    )
    (net (code "43") (name "/139") (class "Default")
      (node (ref "JP3") (pin "27") (pinfunction "27_27") (pintype "passive"))
      (node (ref "U4") (pin "139") (pinfunction "IO,_DIFFIO_R11p_139") (pintype "bidirectional"))
    )
    (net (code "44") (name "/142") (class "Default")
      (node (ref "JP3") (pin "28") (pinfunction "28_28") (pintype "passive"))
      (node (ref "U4") (pin "142") (pinfunction "IO,_DIFFIO_R10n_142") (pintype "bidirectional"))
    )
    (net (code "45") (name "/143") (class "Default")
      (node (ref "JP3") (pin "29") (pinfunction "29_29") (pintype "passive"))
      (node (ref "U4") (pin "143") (pinfunction "IO,_DIFFIO_R10p,_(DQS1R/CQ1R#,DPCLK6)_143") (pintype "bidirectional"))
    )
    (net (code "46") (name "/144") (class "Default")
      (node (ref "JP3") (pin "30") (pinfunction "30_30") (pintype "passive"))
      (node (ref "U4") (pin "144") (pinfunction "IO,_DIFFIO_R9n,_(DEV_OE)_144") (pintype "bidirectional"))
    )
    (net (code "47") (name "/145") (class "Default")
      (node (ref "JP3") (pin "31") (pinfunction "31_31") (pintype "passive"))
      (node (ref "U4") (pin "145") (pinfunction "IO,_DIFFIO_R9p,_(DEV_CLRn)_145") (pintype "bidirectional"))
    )
    (net (code "48") (name "/146") (class "Default")
      (node (ref "JP3") (pin "32") (pinfunction "32_32") (pintype "passive"))
      (node (ref "U4") (pin "146") (pinfunction "IO_146") (pintype "bidirectional"))
    )
    (net (code "49") (name "/147") (class "Default")
      (node (ref "JP3") (pin "33") (pinfunction "33_33") (pintype "passive"))
      (node (ref "U4") (pin "147") (pinfunction "IO,_DIFFIO_R7n_147") (pintype "bidirectional"))
    )
    (net (code "50") (name "/148") (class "Default")
      (node (ref "JP3") (pin "34") (pinfunction "34_34") (pintype "passive"))
      (node (ref "U4") (pin "148") (pinfunction "IO,_DIFFIO_R7p_148") (pintype "bidirectional"))
    )
    (net (code "51") (name "/159") (class "Default")
      (node (ref "JP3") (pin "35") (pinfunction "35_35") (pintype "passive"))
      (node (ref "U4") (pin "159") (pinfunction "IO,_DIFFIO_R5n,_(INIT_DONE)_159") (pintype "bidirectional"))
    )
    (net (code "52") (name "/160") (class "Default")
      (node (ref "JP3") (pin "36") (pinfunction "36_36") (pintype "passive"))
      (node (ref "U4") (pin "160") (pinfunction "IO,_DIFFIO_R5p,_(CRC_ERROR)_160") (pintype "bidirectional"))
    )
    (net (code "53") (name "/161") (class "Default")
      (node (ref "JP3") (pin "37") (pinfunction "37_37") (pintype "passive"))
      (node (ref "U4") (pin "161") (pinfunction "IO_161") (pintype "bidirectional"))
    )
    (net (code "54") (name "/162") (class "Default")
      (node (ref "JP3") (pin "38") (pinfunction "38_38") (pintype "passive"))
      (node (ref "U4") (pin "162") (pinfunction "IO,_DIFFIO_R4n,_(nCEO)_162") (pintype "bidirectional"))
    )
    (net (code "55") (name "/164") (class "Default")
      (node (ref "JP3") (pin "39") (pinfunction "39_39") (pintype "passive"))
      (node (ref "U4") (pin "164") (pinfunction "IO,_DIFFIO_R4p,_(CLKUSR)_164") (pintype "bidirectional"))
    )
    (net (code "56") (name "/166") (class "Default")
      (node (ref "JP3") (pin "40") (pinfunction "40_40") (pintype "passive"))
      (node (ref "U4") (pin "166") (pinfunction "IO,_(DQS0R/CQ1R,DPCLK7)_166") (pintype "bidirectional"))
    )
    (net (code "57") (name "/167") (class "Default")
      (node (ref "JP3") (pin "41") (pinfunction "41_41") (pintype "passive"))
      (node (ref "U4") (pin "167") (pinfunction "IO,_DIFFIO_R3n,_(nWE)_167") (pintype "bidirectional"))
    )
    (net (code "58") (name "/168") (class "Default")
      (node (ref "JP3") (pin "42") (pinfunction "42_42") (pintype "passive"))
      (node (ref "U4") (pin "168") (pinfunction "IO,_DIFFIO_R3p,_(nOE)_168") (pintype "bidirectional"))
    )
    (net (code "59") (name "/169") (class "Default")
      (node (ref "JP3") (pin "43") (pinfunction "43_43") (pintype "passive"))
      (node (ref "U4") (pin "169") (pinfunction "IO,_VREFB6N0_169") (pintype "bidirectional"))
    )
    (net (code "60") (name "/171") (class "Default")
      (node (ref "JP3") (pin "44") (pinfunction "44_44") (pintype "passive"))
      (node (ref "U4") (pin "171") (pinfunction "IO,_(RDY),_(DQ1R)_171") (pintype "bidirectional"))
    )
    (net (code "61") (name "/173") (class "Default")
      (node (ref "JP3") (pin "45") (pinfunction "45_45") (pintype "passive"))
      (node (ref "U4") (pin "173") (pinfunction "IO,_(PADD23)_173") (pintype "bidirectional"))
    )
    (net (code "62") (name "/176") (class "Default")
      (node (ref "JP3") (pin "46") (pinfunction "46_46") (pintype "passive"))
      (node (ref "U4") (pin "176") (pinfunction "IO,_DIFFIO_R1n,_(PADD20),_(DQS2R/CQ3R,CDPCLK5)_176") (pintype "bidirectional"))
    )
    (net (code "63") (name "/177") (class "Default")
      (node (ref "JP3") (pin "47") (pinfunction "47_47") (pintype "passive"))
      (node (ref "U4") (pin "177") (pinfunction "IO,_DIFFIO_R1p_177") (pintype "bidirectional"))
    )
    (net (code "64") (name "/181") (class "Default")
      (node (ref "JP2") (pin "2") (pinfunction "2_2") (pintype "passive"))
      (node (ref "JP3") (pin "55") (pinfunction "55_55") (pintype "passive"))
      (node (ref "U4") (pin "181") (pinfunction "IO_181") (pintype "bidirectional"))
    )
    (net (code "65") (name "/182") (class "Default")
      (node (ref "JP2") (pin "3") (pinfunction "3_3") (pintype "passive"))
      (node (ref "JP3") (pin "54") (pinfunction "54_54") (pintype "passive"))
      (node (ref "U4") (pin "182") (pinfunction "IO,_DIFFIO_T23n_182") (pintype "bidirectional"))
    )
    (net (code "66") (name "/183") (class "Default")
      (node (ref "JP2") (pin "4") (pinfunction "4_4") (pintype "passive"))
      (node (ref "JP3") (pin "53") (pinfunction "53_53") (pintype "passive"))
      (node (ref "U4") (pin "183") (pinfunction "IO,_DIFFIO_T23p,_(DQS0T/CQ1T,CDPCLK6)_183") (pintype "bidirectional"))
    )
    (net (code "67") (name "/184") (class "Default")
      (node (ref "JP2") (pin "5") (pinfunction "5_5") (pintype "passive"))
      (node (ref "JP3") (pin "52") (pinfunction "52_52") (pintype "passive"))
      (node (ref "U4") (pin "184") (pinfunction "IO_184") (pintype "bidirectional"))
    )
    (net (code "68") (name "/185") (class "Default")
      (node (ref "JP2") (pin "6") (pinfunction "6_6") (pintype "passive"))
      (node (ref "JP3") (pin "51") (pinfunction "51_51") (pintype "passive"))
      (node (ref "U4") (pin "185") (pinfunction "IO,_PLL2_CLKOUTn_185") (pintype "bidirectional"))
    )
    (net (code "69") (name "/186") (class "Default")
      (node (ref "JP2") (pin "7") (pinfunction "7_7") (pintype "passive"))
      (node (ref "U4") (pin "186") (pinfunction "IO,_PLL2_CLKOUTp_186") (pintype "bidirectional"))
      (node (ref "U6") (pin "56") (pinfunction "56_56") (pintype "passive"))
    )
    (net (code "70") (name "/187") (class "Default")
      (node (ref "JP2") (pin "8") (pinfunction "8_8") (pintype "passive"))
      (node (ref "JP3") (pin "56") (pinfunction "56_56") (pintype "passive"))
      (node (ref "U4") (pin "187") (pinfunction "IO,_RUP4_187") (pintype "bidirectional"))
      (node (ref "U6") (pin "55") (pinfunction "55_55") (pintype "passive"))
    )
    (net (code "71") (name "/188") (class "Default")
      (node (ref "JP2") (pin "9") (pinfunction "9_9") (pintype "passive"))
      (node (ref "JP3") (pin "57") (pinfunction "57_57") (pintype "passive"))
      (node (ref "U4") (pin "188") (pinfunction "IO,_RDN4_188") (pintype "bidirectional"))
      (node (ref "U6") (pin "54") (pinfunction "54_54") (pintype "passive"))
    )
    (net (code "72") (name "/189") (class "Default")
      (node (ref "JP2") (pin "10") (pinfunction "10_10") (pintype "passive"))
      (node (ref "JP3") (pin "58") (pinfunction "58_58") (pintype "passive"))
      (node (ref "U4") (pin "189") (pinfunction "IO_189") (pintype "bidirectional"))
      (node (ref "U6") (pin "51") (pinfunction "51_51") (pintype "passive"))
    )
    (net (code "73") (name "/194") (class "Default")
      (node (ref "JP2") (pin "11") (pinfunction "11_11") (pintype "passive"))
      (node (ref "JP3") (pin "59") (pinfunction "59_59") (pintype "passive"))
      (node (ref "U4") (pin "194") (pinfunction "IO,_(PADD0),_(DQ5T)_194") (pintype "bidirectional"))
      (node (ref "U6") (pin "49") (pinfunction "49_49") (pintype "passive"))
    )
    (net (code "74") (name "/195") (class "Default")
      (node (ref "JP2") (pin "12") (pinfunction "12_12") (pintype "passive"))
      (node (ref "JP3") (pin "60") (pinfunction "60_60") (pintype "passive"))
      (node (ref "U4") (pin "195") (pinfunction "IO,_VREFB7N0_195") (pintype "bidirectional"))
      (node (ref "U6") (pin "46") (pinfunction "46_46") (pintype "passive"))
    )
    (net (code "75") (name "/196") (class "Default")
      (node (ref "JP2") (pin "13") (pinfunction "13_13") (pintype "passive"))
      (node (ref "JP3") (pin "61") (pinfunction "61_61") (pintype "passive"))
      (node (ref "U4") (pin "196") (pinfunction "IO,_DIFFIO_T19n,_(PADD1)_196") (pintype "bidirectional"))
      (node (ref "U6") (pin "44") (pinfunction "44_44") (pintype "passive"))
    )
    (net (code "76") (name "/197") (class "Default")
      (node (ref "JP2") (pin "14") (pinfunction "14_14") (pintype "passive"))
      (node (ref "JP3") (pin "62") (pinfunction "62_62") (pintype "passive"))
      (node (ref "U4") (pin "197") (pinfunction "IO,_DIFFIO_T19p,_(PADD2),_(DQ5T)_197") (pintype "bidirectional"))
      (node (ref "U6") (pin "40") (pinfunction "40_40") (pintype "passive"))
    )
    (net (code "77") (name "/200") (class "Default")
      (node (ref "JP2") (pin "15") (pinfunction "15_15") (pintype "passive"))
      (node (ref "JP3") (pin "63") (pinfunction "63_63") (pintype "passive"))
      (node (ref "U4") (pin "200") (pinfunction "IO,_(PADD4),_(DQS2T/CQ3T,DPCLK8)_200") (pintype "bidirectional"))
      (node (ref "U6") (pin "38") (pinfunction "38_38") (pintype "passive"))
    )
    (net (code "78") (name "/201") (class "Default")
      (node (ref "JP2") (pin "16") (pinfunction "16_16") (pintype "passive"))
      (node (ref "JP3") (pin "64") (pinfunction "64_64") (pintype "passive"))
      (node (ref "U4") (pin "201") (pinfunction "IO,_(PADD5),_(DQ5T)_201") (pintype "bidirectional"))
      (node (ref "U6") (pin "35") (pinfunction "35_35") (pintype "passive"))
    )
    (net (code "79") (name "/202") (class "Default")
      (node (ref "JP2") (pin "17") (pinfunction "17_17") (pintype "passive"))
      (node (ref "JP3") (pin "65") (pinfunction "65_65") (pintype "passive"))
      (node (ref "U4") (pin "202") (pinfunction "IO,_DIFFIO_T15n,_(PADD7),_(DQ5T)_202") (pintype "bidirectional"))
      (node (ref "U6") (pin "33") (pinfunction "33_33") (pintype "passive"))
    )
    (net (code "80") (name "/203") (class "Default")
      (node (ref "JP2") (pin "18") (pinfunction "18_18") (pintype "passive"))
      (node (ref "JP3") (pin "66") (pinfunction "66_66") (pintype "passive"))
      (node (ref "U4") (pin "203") (pinfunction "IO,_DIFFIO_T15p,_(PADD8)_203") (pintype "bidirectional"))
      (node (ref "U6") (pin "32") (pinfunction "32_32") (pintype "passive"))
    )
    (net (code "81") (name "/207") (class "Default")
      (node (ref "JP2") (pin "19") (pinfunction "19_19") (pintype "passive"))
      (node (ref "U4") (pin "207") (pinfunction "IO,_(PADD12),_(DQS4T/CQ5T,DPCLK9)_207") (pintype "bidirectional"))
      (node (ref "U6") (pin "30") (pinfunction "30_30") (pintype "passive"))
    )
    (net (code "82") (name "/214") (class "Default")
      (node (ref "JP2") (pin "26") (pinfunction "26_26") (pintype "passive"))
      (node (ref "U4") (pin "214") (pinfunction "IO,_(PADD17),_(DQS5T/CQ5T#,DPCLK10)_214") (pintype "bidirectional"))
      (node (ref "U6") (pin "22") (pinfunction "22_22") (pintype "passive"))
    )
    (net (code "83") (name "/216") (class "Default")
      (node (ref "JP2") (pin "27") (pinfunction "27_27") (pintype "passive"))
      (node (ref "JP3") (pin "67") (pinfunction "67_67") (pintype "passive"))
      (node (ref "U4") (pin "216") (pinfunction "IO_216") (pintype "bidirectional"))
      (node (ref "U6") (pin "23") (pinfunction "23_23") (pintype "passive"))
    )
    (net (code "84") (name "/217") (class "Default")
      (node (ref "JP2") (pin "28") (pinfunction "28_28") (pintype "passive"))
      (node (ref "JP3") (pin "68") (pinfunction "68_68") (pintype "passive"))
      (node (ref "U4") (pin "217") (pinfunction "IO,_(DQ5T)_217") (pintype "bidirectional"))
      (node (ref "U6") (pin "24") (pinfunction "24_24") (pintype "passive"))
    )
    (net (code "85") (name "/218") (class "Default")
      (node (ref "JP2") (pin "29") (pinfunction "29_29") (pintype "passive"))
      (node (ref "JP3") (pin "69") (pinfunction "69_69") (pintype "passive"))
      (node (ref "U4") (pin "218") (pinfunction "IO,_DIFFIO_T10n,_(DATA2)_218") (pintype "bidirectional"))
      (node (ref "U6") (pin "25") (pinfunction "25_25") (pintype "passive"))
    )
    (net (code "86") (name "/219") (class "Default")
      (node (ref "JP2") (pin "30") (pinfunction "30_30") (pintype "passive"))
      (node (ref "JP3") (pin "70") (pinfunction "70_70") (pintype "passive"))
      (node (ref "U4") (pin "219") (pinfunction "IO,_DIFFIO_T10p,_(DATA3),_(DQ5T)_219") (pintype "bidirectional"))
      (node (ref "U6") (pin "26") (pinfunction "26_26") (pintype "passive"))
    )
    (net (code "87") (name "/221") (class "Default")
      (node (ref "JP2") (pin "31") (pinfunction "31_31") (pintype "passive"))
      (node (ref "JP3") (pin "71") (pinfunction "71_71") (pintype "passive"))
      (node (ref "U4") (pin "221") (pinfunction "IO,_(DATA4),_(DQ5T)_221") (pintype "bidirectional"))
      (node (ref "U6") (pin "27") (pinfunction "27_27") (pintype "passive"))
    )
    (net (code "88") (name "/223") (class "Default")
      (node (ref "JP2") (pin "32") (pinfunction "32_32") (pintype "passive"))
      (node (ref "JP3") (pin "72") (pinfunction "72_72") (pintype "passive"))
      (node (ref "U4") (pin "223") (pinfunction "IO,_VREFB8N0_223") (pintype "bidirectional"))
      (node (ref "U6") (pin "28") (pinfunction "28_28") (pintype "passive"))
    )
    (net (code "89") (name "/224") (class "Default")
      (node (ref "JP2") (pin "33") (pinfunction "33_33") (pintype "passive"))
      (node (ref "U4") (pin "224") (pinfunction "IO,_(DATA14),_(DQS3T/CQ3T#,DPCLK11)_224") (pintype "bidirectional"))
      (node (ref "U6") (pin "19") (pinfunction "19_19") (pintype "passive"))
    )
    (net (code "90") (name "/226") (class "Default")
      (node (ref "JP2") (pin "34") (pinfunction "34_34") (pintype "passive"))
      (node (ref "U4") (pin "226") (pinfunction "IO,_(DATA5),_(DQ5T)_226") (pintype "bidirectional"))
      (node (ref "U6") (pin "20") (pinfunction "20_20") (pintype "passive"))
    )
    (net (code "91") (name "/230") (class "Default")
      (node (ref "JP2") (pin "35") (pinfunction "35_35") (pintype "passive"))
      (node (ref "U4") (pin "230") (pinfunction "IO,_DIFFIO_T6n_230") (pintype "bidirectional"))
      (node (ref "U6") (pin "17") (pinfunction "17_17") (pintype "passive"))
    )
    (net (code "92") (name "/231") (class "Default")
      (node (ref "JP2") (pin "36") (pinfunction "36_36") (pintype "passive"))
      (node (ref "U4") (pin "231") (pinfunction "IO,_DIFFIO_T6p,_(DATA6),_(DQ5T)_231") (pintype "bidirectional"))
      (node (ref "U6") (pin "18") (pinfunction "18_18") (pintype "passive"))
    )
    (net (code "93") (name "/232") (class "Default")
      (node (ref "JP2") (pin "37") (pinfunction "37_37") (pintype "passive"))
      (node (ref "U4") (pin "232") (pinfunction "IO,_(DATA7),_(DM5T/BWS#5T)_232") (pintype "bidirectional"))
      (node (ref "U6") (pin "13") (pinfunction "13_13") (pintype "passive"))
    )
    (net (code "94") (name "/233") (class "Default")
      (node (ref "JP2") (pin "38") (pinfunction "38_38") (pintype "passive"))
      (node (ref "U4") (pin "233") (pinfunction "IO,_(DATA11)_233") (pintype "bidirectional"))
      (node (ref "U6") (pin "14") (pinfunction "14_14") (pintype "passive"))
    )
    (net (code "95") (name "/234") (class "Default")
      (node (ref "JP2") (pin "39") (pinfunction "39_39") (pintype "passive"))
      (node (ref "U4") (pin "234") (pinfunction "IO,_DIFFIO_T2n_234") (pintype "bidirectional"))
      (node (ref "U6") (pin "11") (pinfunction "11_11") (pintype "passive"))
    )
    (net (code "96") (name "/235") (class "Default")
      (node (ref "JP2") (pin "40") (pinfunction "40_40") (pintype "passive"))
      (node (ref "U4") (pin "235") (pinfunction "IO,_DIFFIO_T2p_235") (pintype "bidirectional"))
      (node (ref "U6") (pin "12") (pinfunction "12_12") (pintype "passive"))
    )
    (net (code "97") (name "/236") (class "Default")
      (node (ref "JP2") (pin "41") (pinfunction "41_41") (pintype "passive"))
      (node (ref "U4") (pin "236") (pinfunction "IO,_(DATA12),_(DQS1T/CQ1T#,CDPCLK7)_236") (pintype "bidirectional"))
      (node (ref "U6") (pin "8") (pinfunction "8_8") (pintype "passive"))
    )
    (net (code "98") (name "/237") (class "Default")
      (node (ref "JP2") (pin "42") (pinfunction "42_42") (pintype "passive"))
      (node (ref "U4") (pin "237") (pinfunction "IO,_DIFFIO_T1n_237") (pintype "bidirectional"))
      (node (ref "U6") (pin "10") (pinfunction "10_10") (pintype "passive"))
    )
    (net (code "99") (name "/238") (class "Default")
      (node (ref "JP2") (pin "43") (pinfunction "43_43") (pintype "passive"))
      (node (ref "U4") (pin "238") (pinfunction "IO,_DIFFIO_T1p_238") (pintype "bidirectional"))
      (node (ref "U6") (pin "6") (pinfunction "6_6") (pintype "passive"))
    )
    (net (code "100") (name "/239") (class "Default")
      (node (ref "JP2") (pin "44") (pinfunction "44_44") (pintype "passive"))
      (node (ref "U4") (pin "239") (pinfunction "IO,_PLL3_CLKOUTn_239") (pintype "bidirectional"))
      (node (ref "U6") (pin "7") (pinfunction "7_7") (pintype "passive"))
    )
    (net (code "101") (name "/240") (class "Default")
      (node (ref "JP2") (pin "45") (pinfunction "45_45") (pintype "passive"))
      (node (ref "U4") (pin "240") (pinfunction "IO,_PLL3_CLKOUTp_240") (pintype "bidirectional"))
      (node (ref "U6") (pin "4") (pinfunction "4_4") (pintype "passive"))
    )
    (net (code "102") (name "/ASDI") (class "Default")
      (node (ref "EPCS") (pin "9") (pinfunction "9_9") (pintype "passive"))
      (node (ref "U10") (pin "5") (pinfunction "5_5") (pintype "passive"))
      (node (ref "U12") (pin "5") (pinfunction "5_5") (pintype "passive"))
      (node (ref "U4") (pin "12") (pinfunction "IO,_(DATA1,_ASDO)_12") (pintype "bidirectional"))
      (node (ref "U7") (pin "15") (pinfunction "15_15") (pintype "passive"))
    )
    (net (code "103") (name "/CLK0") (class "Default")
      (node (ref "R21") (pin "1") (pinfunction "1_1") (pintype "passive"))
      (node (ref "U4") (pin "31") (pinfunction "CLK0,_DIFFCLK_0p_31") (pintype "input"))
    )
    (net (code "104") (name "/CLK1") (class "Default")
      (node (ref "JP1") (pin "23") (pinfunction "23_23") (pintype "passive"))
      (node (ref "U4") (pin "32") (pinfunction "CLK1,_DIFFCLK_0n_32") (pintype "input"))
    )
    (net (code "105") (name "/CLK2") (class "Default")
      (node (ref "JP1") (pin "24") (pinfunction "24_24") (pintype "passive"))
      (node (ref "U4") (pin "33") (pinfunction "CLK2,_DIFFCLK_1p_33") (pintype "input"))
    )
    (net (code "106") (name "/CLK3") (class "Default")
      (node (ref "JP1") (pin "25") (pinfunction "25_25") (pintype "passive"))
      (node (ref "U4") (pin "34") (pinfunction "CLK3,_DIFFCLK_1n_34") (pintype "input"))
    )
    (net (code "107") (name "/CLK4") (class "Default")
      (node (ref "JP3") (pin "22") (pinfunction "22_22") (pintype "passive"))
      (node (ref "U4") (pin "152") (pinfunction "CLK4,_DIFFCLK_2p_152") (pintype "input"))
    )
    (net (code "108") (name "/CLK5") (class "Default")
      (node (ref "JP3") (pin "24") (pinfunction "24_24") (pintype "passive"))
      (node (ref "U4") (pin "151") (pinfunction "CLK5,_DIFFCLK_2n_151") (pintype "input"))
    )
    (net (code "109") (name "/CLK6") (class "Default")
      (node (ref "JP3") (pin "23") (pinfunction "23_23") (pintype "passive"))
      (node (ref "U4") (pin "150") (pinfunction "CLK6,_DIFFCLK_3p_150") (pintype "input"))
    )
    (net (code "110") (name "/CLK7") (class "Default")
      (node (ref "R14") (pin "2") (pinfunction "2_2") (pintype "passive"))
      (node (ref "R15") (pin "2") (pinfunction "2_2") (pintype "passive"))
      (node (ref "U4") (pin "149") (pinfunction "CLK7,_DIFFCLK_3n_149") (pintype "input"))
    )
    (net (code "111") (name "/CLK9") (class "Default")
      (node (ref "JP2") (pin "23") (pinfunction "23_23") (pintype "passive"))
      (node (ref "U4") (pin "210") (pinfunction "CLK9,_DIFFCLK_5p_210") (pintype "input"))
    )
    (net (code "112") (name "/CLK10") (class "Default")
      (node (ref "JP2") (pin "24") (pinfunction "24_24") (pintype "passive"))
      (node (ref "U4") (pin "211") (pinfunction "CLK10,_DIFFCLK_4n_211") (pintype "input"))
    )
    (net (code "113") (name "/CLK11") (class "Default")
      (node (ref "JP2") (pin "25") (pinfunction "25_25") (pintype "passive"))
      (node (ref "U4") (pin "212") (pinfunction "CLK11,_DIFFCLK_4p_212") (pintype "input"))
    )
    (net (code "114") (name "/CLK12") (class "Default")
      (node (ref "JP4") (pin "25") (pinfunction "25_25") (pintype "passive"))
    )
    (net (code "115") (name "/CLK13") (class "Default")
      (node (ref "JP4") (pin "26") (pinfunction "26_26") (pintype "passive"))
      (node (ref "U4") (pin "91") (pinfunction "CLK13,_DIFFCLK_7p_91") (pintype "input"))
    )
    (net (code "116") (name "/CLK14") (class "Default")
      (node (ref "JP4") (pin "23") (pinfunction "23_23") (pintype "passive"))
      (node (ref "R6") (pin "1") (pinfunction "1_1") (pintype "passive"))
      (node (ref "R7") (pin "2") (pinfunction "2_2") (pintype "passive"))
      (node (ref "U4") (pin "90") (pinfunction "CLK14,_DIFFCLK_6n_90") (pintype "input"))
      (node (ref "U5") (pin "2") (pinfunction "2_2") (pintype "passive"))
    )
    (net (code "117") (name "/CLK15") (class "Default")
      (node (ref "JP4") (pin "24") (pinfunction "24_24") (pintype "passive"))
      (node (ref "U4") (pin "89") (pinfunction "CLK15,_DIFFCLK_6p_89") (pintype "input"))
    )
    (net (code "118") (name "/CLKIN2") (class "Default")
      (node (ref "R21") (pin "2") (pinfunction "2_2") (pintype "passive"))
      (node (ref "R23") (pin "2") (pinfunction "2_2") (pintype "passive"))
      (node (ref "U4") (pin "92") (pinfunction "CLK12,_DIFFCLK_7n_92") (pintype "input"))
    )
    (net (code "119") (name "/DATA") (class "Default")
      (node (ref "EPCS") (pin "7") (pinfunction "7_7") (pintype "passive"))
      (node (ref "JP1") (pin "17") (pinfunction "17_17") (pintype "passive"))
      (node (ref "U10") (pin "2") (pinfunction "2_2") (pintype "passive"))
      (node (ref "U12") (pin "7") (pinfunction "7_7") (pintype "passive"))
      (node (ref "U4") (pin "24") (pinfunction "IO,_(DATA0)_24") (pintype "bidirectional"))
      (node (ref "U7") (pin "8") (pinfunction "8_8") (pintype "passive"))
    )
    (net (code "120") (name "/DCLK") (class "Default")
      (node (ref "EPCS") (pin "1") (pinfunction "1_1") (pintype "passive"))
      (node (ref "JP1") (pin "18") (pinfunction "18_18") (pintype "passive"))
      (node (ref "R16") (pin "1") (pinfunction "1_1") (pintype "passive"))
      (node (ref "U10") (pin "6") (pinfunction "6_6") (pintype "passive"))
      (node (ref "U12") (pin "3") (pinfunction "3_3") (pintype "passive"))
      (node (ref "U4") (pin "23") (pinfunction "DCLK_23") (pintype "bidirectional"))
      (node (ref "U7") (pin "16") (pinfunction "16_16") (pintype "passive"))
    )
    (net (code "121") (name "/GND") (class "Default")
      (node (ref "C1") (pin "1") (pinfunction "1_1") (pintype "passive"))
      (node (ref "C10") (pin "1") (pinfunction "1_1") (pintype "passive"))
      (node (ref "C11") (pin "1") (pinfunction "1_1") (pintype "passive"))
      (node (ref "C12") (pin "1") (pinfunction "1_1") (pintype "passive"))
      (node (ref "C13") (pin "1") (pinfunction "1_1") (pintype "passive"))
      (node (ref "C14") (pin "1") (pinfunction "1_1") (pintype "passive"))
      (node (ref "C15") (pin "1") (pinfunction "1_1") (pintype "passive"))
      (node (ref "C16") (pin "1") (pinfunction "1_1") (pintype "passive"))
      (node (ref "C17") (pin "1") (pinfunction "1_1") (pintype "passive"))
      (node (ref "C18") (pin "1") (pinfunction "1_1") (pintype "passive"))
      (node (ref "C19") (pin "1") (pinfunction "1_1") (pintype "passive"))
      (node (ref "C2") (pin "1") (pinfunction "1_1") (pintype "passive"))
      (node (ref "C20") (pin "1") (pinfunction "1_1") (pintype "passive"))
      (node (ref "C21") (pin "1") (pinfunction "1_1") (pintype "passive"))
      (node (ref "C22") (pin "1") (pinfunction "1_1") (pintype "passive"))
      (node (ref "C23") (pin "1") (pinfunction "1_1") (pintype "passive"))
      (node (ref "C24") (pin "1") (pinfunction "1_1") (pintype "passive"))
      (node (ref "C25") (pin "1") (pinfunction "1_1") (pintype "passive"))
      (node (ref "C26") (pin "1") (pinfunction "1_1") (pintype "passive"))
      (node (ref "C27") (pin "1") (pinfunction "1_1") (pintype "passive"))
      (node (ref "C28") (pin "1") (pinfunction "1_1") (pintype "passive"))
      (node (ref "C29") (pin "2") (pinfunction "2_2") (pintype "passive"))
      (node (ref "C3") (pin "2") (pinfunction "2_2") (pintype "passive"))
      (node (ref "C30") (pin "2") (pinfunction "2_2") (pintype "passive"))
      (node (ref "C31") (pin "1") (pinfunction "1_1") (pintype "passive"))
      (node (ref "C32") (pin "1") (pinfunction "1_1") (pintype "passive"))
      (node (ref "C33") (pin "1") (pinfunction "1_1") (pintype "passive"))
      (node (ref "C34") (pin "1") (pinfunction "1_1") (pintype "passive"))
      (node (ref "C35") (pin "1") (pinfunction "1_1") (pintype "passive"))
      (node (ref "C36") (pin "1") (pinfunction "1_1") (pintype "passive"))
      (node (ref "C37") (pin "1") (pinfunction "1_1") (pintype "passive"))
      (node (ref "C38") (pin "1") (pinfunction "1_1") (pintype "passive"))
      (node (ref "C39") (pin "1") (pinfunction "1_1") (pintype "passive"))
      (node (ref "C4") (pin "2") (pinfunction "2_2") (pintype "passive"))
      (node (ref "C40") (pin "2") (pinfunction "2_2") (pintype "passive"))
      (node (ref "C41") (pin "2") (pinfunction "2_2") (pintype "passive"))
      (node (ref "C42") (pin "1") (pinfunction "1_1") (pintype "passive"))
      (node (ref "C43") (pin "1") (pinfunction "1_1") (pintype "passive"))
      (node (ref "C44") (pin "1") (pinfunction "1_1") (pintype "passive"))
      (node (ref "C45") (pin "1") (pinfunction "1_1") (pintype "passive"))
      (node (ref "C46") (pin "1") (pinfunction "1_1") (pintype "passive"))
      (node (ref "C47") (pin "1") (pinfunction "1_1") (pintype "passive"))
      (node (ref "C48") (pin "1") (pinfunction "1_1") (pintype "passive"))
      (node (ref "C49") (pin "1") (pinfunction "1_1") (pintype "passive"))
      (node (ref "C5") (pin "2") (pinfunction "2_2") (pintype "passive"))
      (node (ref "C50") (pin "1") (pinfunction "1_1") (pintype "passive"))
      (node (ref "C51") (pin "1") (pinfunction "1_1") (pintype "passive"))
      (node (ref "C52") (pin "1") (pinfunction "1_1") (pintype "passive"))
      (node (ref "C53") (pin "1") (pinfunction "1_1") (pintype "passive"))
      (node (ref "C54") (pin "1") (pinfunction "1_1") (pintype "passive"))
      (node (ref "C55") (pin "1") (pinfunction "1_1") (pintype "passive"))
      (node (ref "C6") (pin "2") (pinfunction "2_2") (pintype "passive"))
      (node (ref "C7") (pin "1") (pinfunction "1_1") (pintype "passive"))
      (node (ref "C8") (pin "1") (pinfunction "1_1") (pintype "passive"))
      (node (ref "C9") (pin "1") (pinfunction "1_1") (pintype "passive"))
      (node (ref "D5") (pin "1") (pinfunction "A_1") (pintype "passive"))
      (node (ref "EPCS") (pin "10") (pinfunction "10_10") (pintype "passive"))
      (node (ref "EPCS") (pin "2") (pinfunction "2_2") (pintype "passive"))
      (node (ref "JP2") (pin "22") (pinfunction "22_22") (pintype "passive"))
      (node (ref "JP3") (pin "50") (pinfunction "50_50") (pintype "passive"))
      (node (ref "JP4") (pin "1") (pinfunction "1_1") (pintype "passive"))
      (node (ref "JP4") (pin "3") (pinfunction "3_3") (pintype "passive"))
      (node (ref "JP4") (pin "4") (pinfunction "4_4") (pintype "passive"))
      (node (ref "JP4") (pin "47") (pinfunction "47_47") (pintype "passive"))
      (node (ref "JTAG") (pin "10") (pinfunction "10_10") (pintype "passive"))
      (node (ref "JTAG") (pin "2") (pinfunction "2_2") (pintype "passive"))
      (node (ref "PW") (pin "2") (pinfunction "2_2") (pintype "passive"))
      (node (ref "PW") (pin "3") (pinfunction "3_3") (pintype "passive"))
      (node (ref "PWLED") (pin "2") (pinfunction "K_2") (pintype "passive"))
      (node (ref "R19") (pin "1") (pinfunction "1_1") (pintype "passive"))
      (node (ref "R2") (pin "1") (pinfunction "1_1") (pintype "passive"))
      (node (ref "R20") (pin "1") (pinfunction "1_1") (pintype "passive"))
      (node (ref "R8") (pin "1") (pinfunction "1_1") (pintype "passive"))
      (node (ref "RESET") (pin "1") (pinfunction "1_1") (pintype "passive"))
      (node (ref "U1") (pin "1") (pinfunction "1_1") (pintype "passive"))
      (node (ref "U10") (pin "4") (pinfunction "4_4") (pintype "passive"))
      (node (ref "U11") (pin "1") (pinfunction "1_1") (pintype "passive"))
      (node (ref "U11") (pin "8") (pinfunction "8_8") (pintype "passive"))
      (node (ref "U12") (pin "1") (pinfunction "1_1") (pintype "passive"))
      (node (ref "U12") (pin "8") (pinfunction "8_8") (pintype "passive"))
      (node (ref "U2") (pin "3") (pinfunction "3_3") (pintype "passive"))
      (node (ref "U2") (pin "5") (pinfunction "5_5") (pintype "passive"))
      (node (ref "U3") (pin "1") (pinfunction "1_1") (pintype "passive"))
      (node (ref "U4") (pin "102") (pinfunction "GND_102") (pintype "power_in"))
      (node (ref "U4") (pin "105") (pinfunction "GND_105") (pintype "power_in"))
      (node (ref "U4") (pin "11") (pinfunction "GND_11") (pintype "power_in"))
      (node (ref "U4") (pin "116") (pinfunction "GND_116") (pintype "power_in"))
      (node (ref "U4") (pin "122") (pinfunction "GNDA4_122") (pintype "power_in"))
      (node (ref "U4") (pin "125") (pinfunction "GND_125") (pintype "power_in"))
      (node (ref "U4") (pin "130") (pinfunction "GND_130") (pintype "power_in"))
      (node (ref "U4") (pin "138") (pinfunction "GND_138") (pintype "power_in"))
      (node (ref "U4") (pin "141") (pinfunction "GND_141") (pintype "power_in"))
      (node (ref "U4") (pin "155") (pinfunction "MSEL0_155") (pintype "input"))
      (node (ref "U4") (pin "156") (pinfunction "GND_156") (pintype "power_in"))
      (node (ref "U4") (pin "158") (pinfunction "MSEL2_158") (pintype "input"))
      (node (ref "U4") (pin "16") (pinfunction "GND_16") (pintype "power_in"))
      (node (ref "U4") (pin "165") (pinfunction "GND_165") (pintype "power_in"))
      (node (ref "U4") (pin "172") (pinfunction "GND_172") (pintype "power_in"))
      (node (ref "U4") (pin "175") (pinfunction "GND_175") (pintype "power_in"))
      (node (ref "U4") (pin "179") (pinfunction "GNDA2_179") (pintype "power_in"))
      (node (ref "U4") (pin "191") (pinfunction "GND_191") (pintype "power_in"))
      (node (ref "U4") (pin "193") (pinfunction "GND_193") (pintype "power_in"))
      (node (ref "U4") (pin "199") (pinfunction "GND_199") (pintype "power_in"))
      (node (ref "U4") (pin "2") (pinfunction "GNDA3_2") (pintype "power_in"))
      (node (ref "U4") (pin "20") (pinfunction "GND_20") (pintype "power_in"))
      (node (ref "U4") (pin "205") (pinfunction "GND_205") (pintype "power_in"))
      (node (ref "U4") (pin "208") (pinfunction "GND_208") (pintype "power_in"))
      (node (ref "U4") (pin "215") (pinfunction "GND_215") (pintype "power_in"))
      (node (ref "U4") (pin "222") (pinfunction "GND_222") (pintype "power_in"))
      (node (ref "U4") (pin "227") (pinfunction "GND_227") (pintype "power_in"))
      (node (ref "U4") (pin "229") (pinfunction "GND_229") (pintype "power_in"))
      (node (ref "U4") (pin "36") (pinfunction "GND_36") (pintype "power_in"))
      (node (ref "U4") (pin "42") (pinfunction "GND_42") (pintype "power_in"))
      (node (ref "U4") (pin "48") (pinfunction "GND_48") (pintype "power_in"))
      (node (ref "U4") (pin "54") (pinfunction "GND_54") (pintype "power_in"))
      (node (ref "U4") (pin "59") (pinfunction "GNDA1_59") (pintype "power_in"))
      (node (ref "U4") (pin "62") (pinfunction "GND_62") (pintype "power_in"))
      (node (ref "U4") (pin "67") (pinfunction "GND_67") (pintype "power_in"))
      (node (ref "U4") (pin "75") (pinfunction "GND_75") (pintype "power_in"))
      (node (ref "U4") (pin "79") (pinfunction "GND_79") (pintype "power_in"))
      (node (ref "U4") (pin "8") (pinfunction "GND_8") (pintype "power_in"))
      (node (ref "U4") (pin "86") (pinfunction "GND_86") (pintype "power_in"))
      (node (ref "U4") (pin "97") (pinfunction "GND_97") (pintype "power_in"))
      (node (ref "U5") (pin "1") (pinfunction "1_1") (pintype "passive"))
      (node (ref "U6") (pin "2") (pinfunction "2_2") (pintype "passive"))
      (node (ref "U6") (pin "21") (pinfunction "21_21") (pintype "passive"))
      (node (ref "U6") (pin "29") (pinfunction "29_29") (pintype "passive"))
      (node (ref "U6") (pin "42") (pinfunction "42_42") (pintype "passive"))
      (node (ref "U6") (pin "48") (pinfunction "48_48") (pintype "passive"))
      (node (ref "U7") (pin "10") (pinfunction "10_10") (pintype "passive"))
      (node (ref "U8") (pin "12") (pinfunction "12_12") (pintype "passive"))
      (node (ref "U8") (pin "28") (pinfunction "28_28") (pintype "passive"))
      (node (ref "U8") (pin "41") (pinfunction "41_41") (pintype "passive"))
      (node (ref "U8") (pin "46") (pinfunction "46_46") (pintype "passive"))
      (node (ref "U8") (pin "52") (pinfunction "52_52") (pintype "passive"))
      (node (ref "U8") (pin "54") (pinfunction "54_54") (pintype "passive"))
      (node (ref "U8") (pin "6") (pinfunction "6_6") (pintype "passive"))
      (node (ref "X1") (pin "2") (pinfunction "2_2") (pintype "passive"))
      (node (ref "X2") (pin "2") (pinfunction "2_2") (pintype "passive"))
    )
    (net (code "122") (name "/NCE") (class "Default")
      (node (ref "EPCS") (pin "6") (pinfunction "6_6") (pintype "passive"))
      (node (ref "JP1") (pin "19") (pinfunction "19_19") (pintype "passive"))
      (node (ref "R20") (pin "2") (pinfunction "2_2") (pintype "passive"))
      (node (ref "U11") (pin "7") (pinfunction "7_7") (pintype "passive"))
      (node (ref "U4") (pin "30") (pinfunction "nCE_30") (pintype "input"))
    )
    (net (code "123") (name "/NCONFIG") (class "Default")
      (node (ref "EPCS") (pin "5") (pinfunction "5_5") (pintype "passive"))
      (node (ref "JP1") (pin "20") (pinfunction "20_20") (pintype "passive"))
      (node (ref "R13") (pin "1") (pinfunction "1_1") (pintype "passive"))
      (node (ref "U11") (pin "5") (pinfunction "5_5") (pintype "passive"))
      (node (ref "U4") (pin "25") (pinfunction "nCONFIG_25") (pintype "input"))
    )
    (net (code "124") (name "/NCONF_DONE") (class "Default")
      (node (ref "EPCS") (pin "3") (pinfunction "3_3") (pintype "passive"))
      (node (ref "JP1") (pin "15") (pinfunction "15_15") (pintype "passive"))
      (node (ref "R11") (pin "1") (pinfunction "1_1") (pintype "passive"))
      (node (ref "U12") (pin "4") (pinfunction "4_4") (pintype "passive"))
      (node (ref "U4") (pin "153") (pinfunction "CONF_DONE_153") (pintype "bidirectional"))
    )
    (net (code "125") (name "/NCS") (class "Default")
      (node (ref "EPCS") (pin "8") (pinfunction "8_8") (pintype "passive"))
      (node (ref "U10") (pin "1") (pinfunction "1_1") (pintype "passive"))
      (node (ref "U12") (pin "6") (pinfunction "6_6") (pintype "passive"))
      (node (ref "U4") (pin "14") (pinfunction "IO,_(FLASH_nCE,_nCSO)_14") (pintype "bidirectional"))
      (node (ref "U7") (pin "7") (pinfunction "7_7") (pintype "passive"))
    )
    (net (code "126") (name "/NSTATUS") (class "Default")
      (node (ref "JP1") (pin "12") (pinfunction "12_12") (pintype "passive"))
      (node (ref "R12") (pin "1") (pinfunction "1_1") (pintype "passive"))
      (node (ref "U4") (pin "17") (pinfunction "nSTATUS_17") (pintype "bidirectional"))
    )
    (net (code "127") (name "/NetD0_1") (class "Default")
      (node (ref "D0") (pin "1") (pinfunction "A_1") (pintype "passive"))
      (node (ref "D1") (pin "1") (pinfunction "A_1") (pintype "passive"))
      (node (ref "R4") (pin "2") (pinfunction "2_2") (pintype "passive"))
    )
    (net (code "128") (name "/NetD2_1") (class "Default")
      (node (ref "D2") (pin "1") (pinfunction "A_1") (pintype "passive"))
      (node (ref "D3") (pin "1") (pinfunction "A_1") (pintype "passive"))
      (node (ref "R3") (pin "2") (pinfunction "2_2") (pintype "passive"))
    )
    (net (code "129") (name "/NetD5_2") (class "Default")
      (node (ref "D5") (pin "2") (pinfunction "K_2") (pintype "passive"))
      (node (ref "L1") (pin "1") (pinfunction "1_1") (pintype "passive"))
      (node (ref "U2") (pin "2") (pinfunction "2_2") (pintype "passive"))
    )
    (net (code "130") (name "/NetL4_1") (class "Default")
      (node (ref "L4") (pin "1") (pinfunction "1_1") (pintype "passive"))
      (node (ref "X1") (pin "4") (pinfunction "4_4") (pintype "passive"))
    )
    (net (code "131") (name "/NetL7_1") (class "Default")
      (node (ref "L7") (pin "1") (pinfunction "1_1") (pintype "passive"))
      (node (ref "X2") (pin "4") (pinfunction "4_4") (pintype "passive"))
    )
    (net (code "132") (name "/NetPWLED_1") (class "Default")
      (node (ref "PWLED") (pin "1") (pinfunction "A_1") (pintype "passive"))
      (node (ref "R1") (pin "1") (pinfunction "1_1") (pintype "passive"))
    )
    (net (code "133") (name "/NetPW_1") (class "Default")
      (node (ref "PW") (pin "1") (pinfunction "1_1") (pintype "passive"))
      (node (ref "SW") (pin "1") (pinfunction "1_1") (pintype "passive"))
    )
    (net (code "134") (name "/NetR2_2") (class "Default")
      (node (ref "R2") (pin "2") (pinfunction "2_2") (pintype "passive"))
      (node (ref "R5") (pin "2") (pinfunction "2_2") (pintype "passive"))
      (node (ref "U2") (pin "4") (pinfunction "4_4") (pintype "passive"))
    )
    (net (code "135") (name "/NetR6_2") (class "Default")
      (node (ref "R6") (pin "2") (pinfunction "2_2") (pintype "passive"))
      (node (ref "RESET") (pin "2") (pinfunction "2_2") (pintype "passive"))
      (node (ref "U5") (pin "3") (pinfunction "3_3") (pintype "passive"))
    )
    (net (code "136") (name "/NetR8_2") (class "Default")
      (node (ref "R8") (pin "2") (pinfunction "2_2") (pintype "passive"))
      (node (ref "U6") (pin "31") (pinfunction "31_31") (pintype "passive"))
    )
    (net (code "137") (name "/NetR9_2") (class "Default")
      (node (ref "R9") (pin "2") (pinfunction "2_2") (pintype "passive"))
      (node (ref "X1") (pin "1") (pinfunction "1_1") (pintype "passive"))
    )
    (net (code "138") (name "/NetR10_2") (class "Default")
      (node (ref "R10") (pin "2") (pinfunction "2_2") (pintype "passive"))
      (node (ref "U4") (pin "157") (pinfunction "MSEL1_157") (pintype "input"))
    )
    (net (code "139") (name "/NetR14_1") (class "Default")
      (node (ref "R14") (pin "1") (pinfunction "1_1") (pintype "passive"))
      (node (ref "U4") (pin "209") (pinfunction "CLK8,_DIFFCLK_5n_209") (pintype "input"))
    )
    (net (code "140") (name "/NetR15_1") (class "Default")
      (node (ref "R15") (pin "1") (pinfunction "1_1") (pintype "passive"))
      (node (ref "X1") (pin "3") (pinfunction "3_3") (pintype "passive"))
    )
    (net (code "141") (name "/NetR22_2") (class "Default")
      (node (ref "R22") (pin "2") (pinfunction "2_2") (pintype "passive"))
      (node (ref "X2") (pin "1") (pinfunction "1_1") (pintype "passive"))
    )
    (net (code "142") (name "/NetR23_1") (class "Default")
      (node (ref "R23") (pin "1") (pinfunction "1_1") (pintype "passive"))
      (node (ref "X2") (pin "3") (pinfunction "3_3") (pintype "passive"))
    )
    (net (code "143") (name "/SD_A0") (class "Default")
      (node (ref "JP4") (pin "27") (pinfunction "27_27") (pintype "passive"))
      (node (ref "U4") (pin "94") (pinfunction "IO,_DIFFIO_B13n,_(DQ5B)_94") (pintype "bidirectional"))
      (node (ref "U8") (pin "23") (pinfunction "23_23") (pintype "passive"))
    )
    (net (code "144") (name "/SD_A1") (class "Default")
      (node (ref "JP4") (pin "30") (pinfunction "30_30") (pintype "passive"))
      (node (ref "U4") (pin "95") (pinfunction "IO_95") (pintype "bidirectional"))
      (node (ref "U8") (pin "24") (pinfunction "24_24") (pintype "passive"))
    )
    (net (code "145") (name "/SD_A2") (class "Default")
      (node (ref "JP4") (pin "29") (pinfunction "29_29") (pintype "passive"))
      (node (ref "U4") (pin "98") (pinfunction "IO,_DIFFIO_B16p,_(DQ5B)_98") (pintype "bidirectional"))
      (node (ref "U8") (pin "25") (pinfunction "25_25") (pintype "passive"))
    )
    (net (code "146") (name "/SD_A3") (class "Default")
      (node (ref "JP4") (pin "32") (pinfunction "32_32") (pintype "passive"))
      (node (ref "U4") (pin "99") (pinfunction "IO,_DIFFIO_B16n,_(DQS4B/CQ5B,DPCLK4)_99") (pintype "bidirectional"))
      (node (ref "U8") (pin "26") (pinfunction "26_26") (pintype "passive"))
    )
    (net (code "147") (name "/SD_A4") (class "Default")
      (node (ref "JP4") (pin "20") (pinfunction "20_20") (pintype "passive"))
      (node (ref "U4") (pin "84") (pinfunction "IO_84") (pintype "bidirectional"))
      (node (ref "U8") (pin "29") (pinfunction "29_29") (pintype "passive"))
    )
    (net (code "148") (name "/SD_A5") (class "Default")
      (node (ref "JP4") (pin "19") (pinfunction "19_19") (pintype "passive"))
      (node (ref "U4") (pin "83") (pinfunction "IO,_(DQS5B/CQ5B#,DPCLK3)_83") (pintype "bidirectional"))
      (node (ref "U8") (pin "30") (pinfunction "30_30") (pintype "passive"))
    )
    (net (code "149") (name "/SD_A6") (class "Default")
      (node (ref "JP4") (pin "18") (pinfunction "18_18") (pintype "passive"))
      (node (ref "U4") (pin "82") (pinfunction "IO,_DIFFIO_B7n,_(DQ5B)_82") (pintype "bidirectional"))
      (node (ref "U8") (pin "31") (pinfunction "31_31") (pintype "passive"))
    )
    (net (code "150") (name "/SD_A7") (class "Default")
      (node (ref "JP4") (pin "17") (pinfunction "17_17") (pintype "passive"))
      (node (ref "U4") (pin "81") (pinfunction "IO,_DIFFIO_B7p,_(DQ5B)_81") (pintype "bidirectional"))
      (node (ref "U8") (pin "32") (pinfunction "32_32") (pintype "passive"))
    )
    (net (code "151") (name "/SD_A8") (class "Default")
      (node (ref "JP4") (pin "15") (pinfunction "15_15") (pintype "passive"))
      (node (ref "U4") (pin "78") (pinfunction "IO,_(DQS3B/CQ3B#,DPCLK2)_78") (pintype "bidirectional"))
      (node (ref "U8") (pin "33") (pinfunction "33_33") (pintype "passive"))
    )
    (net (code "152") (name "/SD_A9") (class "Default")
      (node (ref "JP4") (pin "16") (pinfunction "16_16") (pintype "passive"))
      (node (ref "U4") (pin "80") (pinfunction "IO,_(DM5B/BWS#5B)_80") (pintype "bidirectional"))
      (node (ref "U8") (pin "34") (pinfunction "34_34") (pintype "passive"))
    )
    (net (code "153") (name "/SD_A10") (class "Default")
      (node (ref "JP4") (pin "28") (pinfunction "28_28") (pintype "passive"))
      (node (ref "U4") (pin "93") (pinfunction "IO,_DIFFIO_B13p,_(DQ5B)_93") (pintype "bidirectional"))
      (node (ref "U8") (pin "22") (pinfunction "22_22") (pintype "passive"))
    )
    (net (code "154") (name "/SD_A11") (class "Default")
      (node (ref "JP4") (pin "13") (pinfunction "13_13") (pintype "passive"))
      (node (ref "U4") (pin "73") (pinfunction "IO_73") (pintype "bidirectional"))
      (node (ref "U8") (pin "35") (pinfunction "35_35") (pintype "passive"))
    )
    (net (code "155") (name "/SD_DQ0") (class "Default")
      (node (ref "JP1") (pin "36") (pinfunction "36_36") (pintype "passive"))
      (node (ref "U4") (pin "37") (pinfunction "IO,_DIFFIO_L8p,_(DQ1L)_37") (pintype "bidirectional"))
      (node (ref "U8") (pin "2") (pinfunction "2_2") (pintype "passive"))
    )
    (net (code "156") (name "/SD_DQ1") (class "Default")
      (node (ref "JP1") (pin "37") (pinfunction "37_37") (pintype "passive"))
      (node (ref "U4") (pin "38") (pinfunction "IO,_DIFFIO_L8n,_(DQ1L)_38") (pintype "bidirectional"))
      (node (ref "U8") (pin "4") (pinfunction "4_4") (pintype "passive"))
    )
    (net (code "157") (name "/SD_DQ2") (class "Default")
      (node (ref "JP1") (pin "38") (pinfunction "38_38") (pintype "passive"))
      (node (ref "U4") (pin "39") (pinfunction "IO_39") (pintype "bidirectional"))
      (node (ref "U8") (pin "5") (pinfunction "5_5") (pintype "passive"))
    )
    (net (code "158") (name "/SD_DQ3") (class "Default")
      (node (ref "JP1") (pin "39") (pinfunction "39_39") (pintype "passive"))
      (node (ref "U4") (pin "41") (pinfunction "IO,_DIFFIO_L10p,_(DQ1L)_41") (pintype "bidirectional"))
      (node (ref "U8") (pin "7") (pinfunction "7_7") (pintype "passive"))
    )
    (net (code "159") (name "/SD_DQ4") (class "Default")
      (node (ref "JP1") (pin "40") (pinfunction "40_40") (pintype "passive"))
      (node (ref "U4") (pin "43") (pinfunction "IO,_DIFFIO_L10n,_(DQ1L)_43") (pintype "bidirectional"))
      (node (ref "U8") (pin "8") (pinfunction "8_8") (pintype "passive"))
    )
    (net (code "160") (name "/SD_DQ5") (class "Default")
      (node (ref "JP1") (pin "41") (pinfunction "41_41") (pintype "passive"))
      (node (ref "U4") (pin "44") (pinfunction "IO,_DIFFIO_L11p,_(DQS1L/CQ1L#,DPCLK1)_44") (pintype "bidirectional"))
      (node (ref "U8") (pin "10") (pinfunction "10_10") (pintype "passive"))
    )
    (net (code "161") (name "/SD_DQ6") (class "Default")
      (node (ref "JP1") (pin "42") (pinfunction "42_42") (pintype "passive"))
      (node (ref "U4") (pin "45") (pinfunction "IO,_DIFFIO_L11n,_(DQ1L)_45") (pintype "bidirectional"))
      (node (ref "U8") (pin "11") (pinfunction "11_11") (pintype "passive"))
    )
    (net (code "162") (name "/SD_DQ7") (class "Default")
      (node (ref "JP1") (pin "43") (pinfunction "43_43") (pintype "passive"))
      (node (ref "U4") (pin "46") (pinfunction "IO,_VREFB2N0_46") (pintype "bidirectional"))
      (node (ref "U8") (pin "13") (pinfunction "13_13") (pintype "passive"))
    )
    (net (code "163") (name "/SD_DQ8") (class "Default")
      (node (ref "JP4") (pin "9") (pinfunction "9_9") (pintype "passive"))
      (node (ref "U4") (pin "69") (pinfunction "IO,_PLL1_CLKOUTp_69") (pintype "bidirectional"))
      (node (ref "U8") (pin "42") (pinfunction "42_42") (pintype "passive"))
    )
    (net (code "164") (name "/SD_DQ9") (class "Default")
      (node (ref "JP4") (pin "10") (pinfunction "10_10") (pintype "passive"))
      (node (ref "U4") (pin "70") (pinfunction "IO,_PLL1_CLKOUTn_70") (pintype "bidirectional"))
      (node (ref "U8") (pin "44") (pinfunction "44_44") (pintype "passive"))
    )
    (net (code "165") (name "/SD_DQ10") (class "Default")
      (node (ref "JP4") (pin "7") (pinfunction "7_7") (pintype "passive"))
      (node (ref "U4") (pin "65") (pinfunction "IO_65") (pintype "bidirectional"))
      (node (ref "U8") (pin "45") (pinfunction "45_45") (pintype "passive"))
    )
    (net (code "166") (name "/SD_DQ11") (class "Default")
      (node (ref "JP4") (pin "8") (pinfunction "8_8") (pintype "passive"))
      (node (ref "U4") (pin "68") (pinfunction "IO,_(DQS1B/CQ1B#,CDPCLK2)_68") (pintype "bidirectional"))
      (node (ref "U8") (pin "47") (pinfunction "47_47") (pintype "passive"))
    )
    (net (code "167") (name "/SD_DQ12") (class "Default")
      (node (ref "JP4") (pin "5") (pinfunction "5_5") (pintype "passive"))
      (node (ref "U4") (pin "63") (pinfunction "IO,_DIFFIO_B2p_63") (pintype "bidirectional"))
      (node (ref "U8") (pin "48") (pinfunction "48_48") (pintype "passive"))
    )
    (net (code "168") (name "/SD_DQ13") (class "Default")
      (node (ref "JP4") (pin "6") (pinfunction "6_6") (pintype "passive"))
      (node (ref "U4") (pin "64") (pinfunction "IO,_DIFFIO_B2n_64") (pintype "bidirectional"))
      (node (ref "U8") (pin "50") (pinfunction "50_50") (pintype "passive"))
    )
    (net (code "169") (name "/SD_DQ14") (class "Default")
      (node (ref "JP1") (pin "49") (pinfunction "49_49") (pintype "passive"))
      (node (ref "U4") (pin "56") (pinfunction "IO,_DIFFIO_L15p_56") (pintype "bidirectional"))
      (node (ref "U8") (pin "51") (pinfunction "51_51") (pintype "passive"))
    )
    (net (code "170") (name "/SD_DQ15") (class "Default")
      (node (ref "JP1") (pin "50") (pinfunction "50_50") (pintype "passive"))
      (node (ref "U4") (pin "57") (pinfunction "IO,_DIFFIO_L15n,_(DQ1L)_57") (pintype "bidirectional"))
      (node (ref "U8") (pin "53") (pinfunction "53_53") (pintype "passive"))
    )
    (net (code "171") (name "/TCK") (class "Default")
      (node (ref "JTAG") (pin "1") (pinfunction "1_1") (pintype "passive"))
      (node (ref "R19") (pin "2") (pinfunction "2_2") (pintype "passive"))
      (node (ref "U11") (pin "4") (pinfunction "4_4") (pintype "passive"))
      (node (ref "U4") (pin "27") (pinfunction "TCK_27") (pintype "input"))
    )
    (net (code "172") (name "/TDI") (class "Default")
      (node (ref "JTAG") (pin "9") (pinfunction "9_9") (pintype "passive"))
      (node (ref "R17") (pin "1") (pinfunction "1_1") (pintype "passive"))
      (node (ref "U11") (pin "6") (pinfunction "6_6") (pintype "passive"))
      (node (ref "U4") (pin "26") (pinfunction "TDI_26") (pintype "input"))
    )
    (net (code "173") (name "/TDO") (class "Default")
      (node (ref "JTAG") (pin "3") (pinfunction "3_3") (pintype "passive"))
      (node (ref "U11") (pin "3") (pinfunction "3_3") (pintype "passive"))
      (node (ref "U4") (pin "29") (pinfunction "TDO_29") (pintype "output"))
    )
    (net (code "174") (name "/TMS") (class "Default")
      (node (ref "JTAG") (pin "5") (pinfunction "5_5") (pintype "passive"))
      (node (ref "R18") (pin "1") (pinfunction "1_1") (pintype "passive"))
      (node (ref "U11") (pin "2") (pinfunction "2_2") (pintype "passive"))
      (node (ref "U4") (pin "28") (pinfunction "TMS_28") (pintype "input"))
    )
    (net (code "175") (name "/VCC_1.2") (class "Default")
      (node (ref "C10") (pin "2") (pinfunction "2_2") (pintype "passive"))
      (node (ref "C12") (pin "2") (pinfunction "2_2") (pintype "passive"))
      (node (ref "C14") (pin "2") (pinfunction "2_2") (pintype "passive"))
      (node (ref "C15") (pin "2") (pinfunction "2_2") (pintype "passive"))
      (node (ref "C17") (pin "2") (pinfunction "2_2") (pintype "passive"))
      (node (ref "C18") (pin "2") (pinfunction "2_2") (pintype "passive"))
      (node (ref "C27") (pin "2") (pinfunction "2_2") (pintype "passive"))
      (node (ref "C28") (pin "2") (pinfunction "2_2") (pintype "passive"))
      (node (ref "C33") (pin "2") (pinfunction "2_2") (pintype "passive"))
      (node (ref "C34") (pin "2") (pinfunction "2_2") (pintype "passive"))
      (node (ref "C37") (pin "2") (pinfunction "2_2") (pintype "passive"))
      (node (ref "C44") (pin "2") (pinfunction "2_2") (pintype "passive"))
      (node (ref "C48") (pin "2") (pinfunction "2_2") (pintype "passive"))
      (node (ref "C5") (pin "1") (pinfunction "1_1") (pintype "passive"))
      (node (ref "C50") (pin "2") (pinfunction "2_2") (pintype "passive"))
      (node (ref "C51") (pin "2") (pinfunction "2_2") (pintype "passive"))
      (node (ref "C53") (pin "2") (pinfunction "2_2") (pintype "passive"))
      (node (ref "C55") (pin "2") (pinfunction "2_2") (pintype "passive"))
      (node (ref "C7") (pin "2") (pinfunction "2_2") (pintype "passive"))
      (node (ref "C8") (pin "2") (pinfunction "2_2") (pintype "passive"))
      (node (ref "L1") (pin "2") (pinfunction "2_2") (pintype "passive"))
      (node (ref "R5") (pin "1") (pinfunction "1_1") (pintype "passive"))
      (node (ref "U4") (pin "1") (pinfunction "VCCD_PLL3_1") (pintype "power_in"))
      (node (ref "U4") (pin "10") (pinfunction "VCCINT_10") (pintype "power_in"))
      (node (ref "U4") (pin "101") (pinfunction "VCCINT_101") (pintype "power_in"))
      (node (ref "U4") (pin "115") (pinfunction "VCCINT_115") (pintype "power_in"))
      (node (ref "U4") (pin "121") (pinfunction "VCCD_PLL4_121") (pintype "power_in"))
      (node (ref "U4") (pin "129") (pinfunction "VCCINT_129") (pintype "power_in"))
      (node (ref "U4") (pin "140") (pinfunction "VCCINT_140") (pintype "power_in"))
      (node (ref "U4") (pin "163") (pinfunction "VCCINT_163") (pintype "power_in"))
      (node (ref "U4") (pin "174") (pinfunction "VCCINT_174") (pintype "power_in"))
      (node (ref "U4") (pin "180") (pinfunction "VCCD_PLL2_180") (pintype "power_in"))
      (node (ref "U4") (pin "19") (pinfunction "VCCINT_19") (pintype "power_in"))
      (node (ref "U4") (pin "190") (pinfunction "VCCINT_190") (pintype "power_in"))
      (node (ref "U4") (pin "198") (pinfunction "VCCINT_198") (pintype "power_in"))
      (node (ref "U4") (pin "204") (pinfunction "VCCINT_204") (pintype "power_in"))
      (node (ref "U4") (pin "220") (pinfunction "VCCINT_220") (pintype "power_in"))
      (node (ref "U4") (pin "228") (pinfunction "VCCINT_228") (pintype "power_in"))
      (node (ref "U4") (pin "40") (pinfunction "VCCINT_40") (pintype "power_in"))
      (node (ref "U4") (pin "53") (pinfunction "VCCINT_53") (pintype "power_in"))
      (node (ref "U4") (pin "60") (pinfunction "VCCD_PLL1_60") (pintype "power_in"))
      (node (ref "U4") (pin "61") (pinfunction "VCCINT_61") (pintype "power_in"))
      (node (ref "U4") (pin "74") (pinfunction "VCCINT_74") (pintype "power_in"))
      (node (ref "U4") (pin "85") (pinfunction "VCCINT_85") (pintype "power_in"))
    )
    (net (code "176") (name "/VCC_2.5") (class "Default")
      (node (ref "C4") (pin "1") (pinfunction "1_1") (pintype "passive"))
      (node (ref "JP2") (pin "49") (pinfunction "49_49") (pintype "passive"))
      (node (ref "JP2") (pin "50") (pinfunction "50_50") (pintype "passive"))
      (node (ref "L2") (pin "1") (pinfunction "1_1") (pintype "passive"))
      (node (ref "L3") (pin "1") (pinfunction "1_1") (pintype "passive"))
      (node (ref "L5") (pin "1") (pinfunction "1_1") (pintype "passive"))
      (node (ref "L6") (pin "1") (pinfunction "1_1") (pintype "passive"))
      (node (ref "U1") (pin "2") (pinfunction "2_2") (pintype "passive"))
    )
    (net (code "177") (name "/VCC_3.3") (class "Default")
      (node (ref "C11") (pin "2") (pinfunction "2_2") (pintype "passive"))
      (node (ref "C13") (pin "2") (pinfunction "2_2") (pintype "passive"))
      (node (ref "C16") (pin "2") (pinfunction "2_2") (pintype "passive"))
      (node (ref "C19") (pin "2") (pinfunction "2_2") (pintype "passive"))
      (node (ref "C2") (pin "2") (pinfunction "2_2") (pintype "passive"))
      (node (ref "C20") (pin "2") (pinfunction "2_2") (pintype "passive"))
      (node (ref "C21") (pin "2") (pinfunction "2_2") (pintype "passive"))
      (node (ref "C22") (pin "2") (pinfunction "2_2") (pintype "passive"))
      (node (ref "C31") (pin "2") (pinfunction "2_2") (pintype "passive"))
      (node (ref "C32") (pin "2") (pinfunction "2_2") (pintype "passive"))
      (node (ref "C35") (pin "2") (pinfunction "2_2") (pintype "passive"))
      (node (ref "C36") (pin "2") (pinfunction "2_2") (pintype "passive"))
      (node (ref "C45") (pin "2") (pinfunction "2_2") (pintype "passive"))
      (node (ref "C46") (pin "2") (pinfunction "2_2") (pintype "passive"))
      (node (ref "C47") (pin "2") (pinfunction "2_2") (pintype "passive"))
      (node (ref "C49") (pin "2") (pinfunction "2_2") (pintype "passive"))
      (node (ref "C52") (pin "2") (pinfunction "2_2") (pintype "passive"))
      (node (ref "C54") (pin "2") (pinfunction "2_2") (pintype "passive"))
      (node (ref "C6") (pin "1") (pinfunction "1_1") (pintype "passive"))
      (node (ref "C9") (pin "2") (pinfunction "2_2") (pintype "passive"))
      (node (ref "EPCS") (pin "4") (pinfunction "4_4") (pintype "passive"))
      (node (ref "JP1") (pin "2") (pinfunction "2_2") (pintype "passive"))
      (node (ref "JP1") (pin "31") (pinfunction "31_31") (pintype "passive"))
      (node (ref "JP3") (pin "48") (pinfunction "48_48") (pintype "passive"))
      (node (ref "JP4") (pin "2") (pinfunction "2_2") (pintype "passive"))
      (node (ref "JTAG") (pin "4") (pinfunction "4_4") (pintype "passive"))
      (node (ref "L4") (pin "2") (pinfunction "2_2") (pintype "passive"))
      (node (ref "L7") (pin "2") (pinfunction "2_2") (pintype "passive"))
      (node (ref "R10") (pin "1") (pinfunction "1_1") (pintype "passive"))
      (node (ref "R11") (pin "2") (pinfunction "2_2") (pintype "passive"))
      (node (ref "R12") (pin "2") (pinfunction "2_2") (pintype "passive"))
      (node (ref "R13") (pin "2") (pinfunction "2_2") (pintype "passive"))
      (node (ref "R16") (pin "2") (pinfunction "2_2") (pintype "passive"))
      (node (ref "R17") (pin "2") (pinfunction "2_2") (pintype "passive"))
      (node (ref "R18") (pin "2") (pinfunction "2_2") (pintype "passive"))
      (node (ref "R22") (pin "1") (pinfunction "1_1") (pintype "passive"))
      (node (ref "R3") (pin "1") (pinfunction "1_1") (pintype "passive"))
      (node (ref "R4") (pin "1") (pinfunction "1_1") (pintype "passive"))
      (node (ref "R7") (pin "1") (pinfunction "1_1") (pintype "passive"))
      (node (ref "R9") (pin "1") (pinfunction "1_1") (pintype "passive"))
      (node (ref "U10") (pin "3") (pinfunction "3_3") (pintype "passive"))
      (node (ref "U10") (pin "7") (pinfunction "7_7") (pintype "passive"))
      (node (ref "U10") (pin "8") (pinfunction "8_8") (pintype "passive"))
      (node (ref "U3") (pin "2") (pinfunction "2_2") (pintype "passive"))
      (node (ref "U4") (pin "104") (pinfunction "VCCIO4_104") (pintype "power_in"))
      (node (ref "U4") (pin "124") (pinfunction "VCCIO5_124") (pintype "power_in"))
      (node (ref "U4") (pin "136") (pinfunction "VCCIO5_136") (pintype "power_in"))
      (node (ref "U4") (pin "15") (pinfunction "VCCIO1_15") (pintype "power_in"))
      (node (ref "U4") (pin "154") (pinfunction "VCCIO6_154") (pintype "power_in"))
      (node (ref "U4") (pin "170") (pinfunction "VCCIO6_170") (pintype "power_in"))
      (node (ref "U4") (pin "192") (pinfunction "VCCIO7_192") (pintype "power_in"))
      (node (ref "U4") (pin "206") (pinfunction "VCCIO7_206") (pintype "power_in"))
      (node (ref "U4") (pin "213") (pinfunction "VCCIO8_213") (pintype "power_in"))
      (node (ref "U4") (pin "225") (pinfunction "VCCIO8_225") (pintype "power_in"))
      (node (ref "U4") (pin "35") (pinfunction "VCCIO2_35") (pintype "power_in"))
      (node (ref "U4") (pin "47") (pinfunction "VCCIO2_47") (pintype "power_in"))
      (node (ref "U4") (pin "66") (pinfunction "VCCIO3_66") (pintype "power_in"))
      (node (ref "U4") (pin "7") (pinfunction "VCCIO1_7") (pintype "power_in"))
      (node (ref "U4") (pin "77") (pinfunction "VCCIO3_77") (pintype "power_in"))
      (node (ref "U4") (pin "96") (pinfunction "VCCIO4_96") (pintype "power_in"))
      (node (ref "U5") (pin "4") (pinfunction "4_4") (pintype "passive"))
      (node (ref "U6") (pin "15") (pinfunction "15_15") (pintype "passive"))
      (node (ref "U6") (pin "16") (pinfunction "16_16") (pintype "passive"))
      (node (ref "U6") (pin "37") (pinfunction "37_37") (pintype "passive"))
      (node (ref "U6") (pin "43") (pinfunction "43_43") (pintype "passive"))
      (node (ref "U6") (pin "9") (pinfunction "9_9") (pintype "passive"))
      (node (ref "U7") (pin "1") (pinfunction "1_1") (pintype "passive"))
      (node (ref "U7") (pin "2") (pinfunction "2_2") (pintype "passive"))
      (node (ref "U7") (pin "9") (pinfunction "9_9") (pintype "passive"))
      (node (ref "U8") (pin "1") (pinfunction "1_1") (pintype "passive"))
      (node (ref "U8") (pin "14") (pinfunction "14_14") (pintype "passive"))
      (node (ref "U8") (pin "27") (pinfunction "27_27") (pintype "passive"))
      (node (ref "U8") (pin "3") (pinfunction "3_3") (pintype "passive"))
      (node (ref "U8") (pin "43") (pinfunction "43_43") (pintype "passive"))
      (node (ref "U8") (pin "49") (pinfunction "49_49") (pintype "passive"))
      (node (ref "U8") (pin "9") (pinfunction "9_9") (pintype "passive"))
    )
    (net (code "178") (name "/VCC_5") (class "Default")
      (node (ref "C1") (pin "2") (pinfunction "2_2") (pintype "passive"))
      (node (ref "C3") (pin "1") (pinfunction "1_1") (pintype "passive"))
      (node (ref "JP2") (pin "1") (pinfunction "1_1") (pintype "passive"))
      (node (ref "JP3") (pin "49") (pinfunction "49_49") (pintype "passive"))
      (node (ref "R1") (pin "2") (pinfunction "2_2") (pintype "passive"))
      (node (ref "SW") (pin "2") (pinfunction "2_2") (pintype "passive"))
      (node (ref "U1") (pin "3") (pinfunction "3_3") (pintype "passive"))
      (node (ref "U2") (pin "1") (pinfunction "1_1") (pintype "passive"))
      (node (ref "U3") (pin "3") (pinfunction "3_3") (pintype "passive"))
    )
    (net (code "179") (name "/VCC_PLL1") (class "Default")
      (node (ref "C38") (pin "2") (pinfunction "2_2") (pintype "passive"))
      (node (ref "C39") (pin "2") (pinfunction "2_2") (pintype "passive"))
      (node (ref "C40") (pin "1") (pinfunction "1_1") (pintype "passive"))
      (node (ref "L5") (pin "2") (pinfunction "2_2") (pintype "passive"))
      (node (ref "U4") (pin "58") (pinfunction "VCCA1_58") (pintype "power_in"))
    )
    (net (code "180") (name "/VCC_PLL2") (class "Default")
      (node (ref "C25") (pin "2") (pinfunction "2_2") (pintype "passive"))
      (node (ref "C26") (pin "2") (pinfunction "2_2") (pintype "passive"))
      (node (ref "C30") (pin "1") (pinfunction "1_1") (pintype "passive"))
      (node (ref "L3") (pin "2") (pinfunction "2_2") (pintype "passive"))
      (node (ref "U4") (pin "178") (pinfunction "VCCA2_178") (pintype "power_in"))
    )
    (net (code "181") (name "/VCC_PLL3") (class "Default")
      (node (ref "C23") (pin "2") (pinfunction "2_2") (pintype "passive"))
      (node (ref "C24") (pin "2") (pinfunction "2_2") (pintype "passive"))
      (node (ref "C29") (pin "1") (pinfunction "1_1") (pintype "passive"))
      (node (ref "L2") (pin "2") (pinfunction "2_2") (pintype "passive"))
      (node (ref "U4") (pin "3") (pinfunction "VCCA3_3") (pintype "power_in"))
    )
    (net (code "182") (name "/VCC_PLL4") (class "Default")
      (node (ref "C41") (pin "1") (pinfunction "1_1") (pintype "passive"))
      (node (ref "C42") (pin "2") (pinfunction "2_2") (pintype "passive"))
      (node (ref "C43") (pin "2") (pinfunction "2_2") (pintype "passive"))
      (node (ref "L6") (pin "2") (pinfunction "2_2") (pintype "passive"))
      (node (ref "U4") (pin "123") (pinfunction "VCCA4_123") (pintype "power_in"))
    )
    (net (code "183") (name "unconnected-(JP1-Pad1)") (class "Default")
      (node (ref "JP1") (pin "1") (pinfunction "1_1") (pintype "passive+no_connect"))
    )
    (net (code "184") (name "unconnected-(JP1-Pad7)") (class "Default")
      (node (ref "JP1") (pin "7") (pinfunction "7_7") (pintype "passive+no_connect"))
    )
    (net (code "185") (name "unconnected-(JP1-Pad8)") (class "Default")
      (node (ref "JP1") (pin "8") (pinfunction "8_8") (pintype "passive+no_connect"))
    )
    (net (code "186") (name "unconnected-(JP1-Pad9)") (class "Default")
      (node (ref "JP1") (pin "9") (pinfunction "9_9") (pintype "passive+no_connect"))
    )
    (net (code "187") (name "unconnected-(JP1-Pad11)") (class "Default")
      (node (ref "JP1") (pin "11") (pinfunction "11_11") (pintype "passive+no_connect"))
    )
    (net (code "188") (name "unconnected-(JP1-Pad21)") (class "Default")
      (node (ref "JP1") (pin "21") (pinfunction "21_21") (pintype "passive+no_connect"))
    )
    (net (code "189") (name "unconnected-(JP1-Pad22)") (class "Default")
      (node (ref "JP1") (pin "22") (pinfunction "22_22") (pintype "passive+no_connect"))
    )
    (net (code "190") (name "unconnected-(JP1-Pad26)") (class "Default")
      (node (ref "JP1") (pin "26") (pinfunction "26_26") (pintype "passive+no_connect"))
    )
    (net (code "191") (name "unconnected-(JP1-Pad27)") (class "Default")
      (node (ref "JP1") (pin "27") (pinfunction "27_27") (pintype "passive+no_connect"))
    )
    (net (code "192") (name "unconnected-(JP1-Pad28)") (class "Default")
      (node (ref "JP1") (pin "28") (pinfunction "28_28") (pintype "passive+no_connect"))
    )
    (net (code "193") (name "unconnected-(JP1-Pad29)") (class "Default")
      (node (ref "JP1") (pin "29") (pinfunction "29_29") (pintype "passive+no_connect"))
    )
    (net (code "194") (name "unconnected-(JP1-Pad30)") (class "Default")
      (node (ref "JP1") (pin "30") (pinfunction "30_30") (pintype "passive+no_connect"))
    )
    (net (code "195") (name "unconnected-(JP1-Pad32)") (class "Default")
      (node (ref "JP1") (pin "32") (pinfunction "32_32") (pintype "passive+no_connect"))
    )
    (net (code "196") (name "unconnected-(JP1-Pad33)") (class "Default")
      (node (ref "JP1") (pin "33") (pinfunction "33_33") (pintype "passive+no_connect"))
    )
    (net (code "197") (name "unconnected-(JP1-Pad34)") (class "Default")
      (node (ref "JP1") (pin "34") (pinfunction "34_34") (pintype "passive+no_connect"))
    )
    (net (code "198") (name "unconnected-(JP1-Pad35)") (class "Default")
      (node (ref "JP1") (pin "35") (pinfunction "35_35") (pintype "passive+no_connect"))
    )
    (net (code "199") (name "unconnected-(JP2-Pad20)") (class "Default")
      (node (ref "JP2") (pin "20") (pinfunction "20_20") (pintype "passive"))
    )
    (net (code "200") (name "unconnected-(JP2-Pad21)") (class "Default")
      (node (ref "JP2") (pin "21") (pinfunction "21_21") (pintype "passive"))
    )
    (net (code "201") (name "unconnected-(JP3-Pad25)") (class "Default")
      (node (ref "JP3") (pin "25") (pinfunction "25_25") (pintype "passive+no_connect"))
    )
    (net (code "202") (name "unconnected-(JP4-Pad48)") (class "Default")
      (node (ref "JP4") (pin "48") (pinfunction "48_48") (pintype "passive+no_connect"))
    )
    (net (code "203") (name "unconnected-(JP4-Pad49)") (class "Default")
      (node (ref "JP4") (pin "49") (pinfunction "49_49") (pintype "passive+no_connect"))
    )
    (net (code "204") (name "unconnected-(JP4-Pad50)") (class "Default")
      (node (ref "JP4") (pin "50") (pinfunction "50_50") (pintype "passive+no_connect"))
    )
    (net (code "205") (name "unconnected-(JTAG-Pad6)") (class "Default")
      (node (ref "JTAG") (pin "6") (pinfunction "6_6") (pintype "passive+no_connect"))
    )
    (net (code "206") (name "unconnected-(JTAG-Pad7)") (class "Default")
      (node (ref "JTAG") (pin "7") (pinfunction "7_7") (pintype "passive+no_connect"))
    )
    (net (code "207") (name "unconnected-(JTAG-Pad8)") (class "Default")
      (node (ref "JTAG") (pin "8") (pinfunction "8_8") (pintype "passive+no_connect"))
    )
    (net (code "208") (name "unconnected-(SW-Pad3)") (class "Default")
      (node (ref "SW") (pin "3") (pinfunction "3_3") (pintype "passive+no_connect"))
    )
    (net (code "209") (name "unconnected-(U1-Pad4)") (class "Default")
      (node (ref "U1") (pin "4") (pinfunction "4_4") (pintype "passive+no_connect"))
    )
    (net (code "210") (name "unconnected-(U6-Pad34)") (class "Default")
      (node (ref "U6") (pin "34") (pinfunction "34_34") (pintype "passive+no_connect"))
    )
    (net (code "211") (name "unconnected-(U6-Pad36)") (class "Default")
      (node (ref "U6") (pin "36") (pinfunction "36_36") (pintype "passive+no_connect"))
    )
    (net (code "212") (name "unconnected-(U6-Pad39)") (class "Default")
      (node (ref "U6") (pin "39") (pinfunction "39_39") (pintype "passive+no_connect"))
    )
    (net (code "213") (name "unconnected-(U6-Pad41)") (class "Default")
      (node (ref "U6") (pin "41") (pinfunction "41_41") (pintype "passive+no_connect"))
    )
    (net (code "214") (name "unconnected-(U6-Pad45)") (class "Default")
      (node (ref "U6") (pin "45") (pinfunction "45_45") (pintype "passive+no_connect"))
    )
    (net (code "215") (name "unconnected-(U6-Pad47)") (class "Default")
      (node (ref "U6") (pin "47") (pinfunction "47_47") (pintype "passive+no_connect"))
    )
    (net (code "216") (name "unconnected-(U6-Pad50)") (class "Default")
      (node (ref "U6") (pin "50") (pinfunction "50_50") (pintype "passive+no_connect"))
    )
    (net (code "217") (name "unconnected-(U6-Pad52)") (class "Default")
      (node (ref "U6") (pin "52") (pinfunction "52_52") (pintype "passive+no_connect"))
    )
    (net (code "218") (name "unconnected-(U6-Pad53)") (class "Default")
      (node (ref "U6") (pin "53") (pinfunction "53_53") (pintype "passive+no_connect"))
    )
    (net (code "219") (name "unconnected-(U6-Pad57)") (class "Default")
      (node (ref "U6") (pin "57") (pinfunction "57_57") (pintype "passive+no_connect"))
    )
    (net (code "220") (name "unconnected-(U6-Pad58)") (class "Default")
      (node (ref "U6") (pin "58") (pinfunction "58_58") (pintype "passive+no_connect"))
    )
    (net (code "221") (name "unconnected-(U6-Pad59)") (class "Default")
      (node (ref "U6") (pin "59") (pinfunction "59_59") (pintype "passive+no_connect"))
    )
    (net (code "222") (name "unconnected-(U6-Pad60)") (class "Default")
      (node (ref "U6") (pin "60") (pinfunction "60_60") (pintype "passive+no_connect"))
    )
    (net (code "223") (name "unconnected-(U7-Pad3)") (class "Default")
      (node (ref "U7") (pin "3") (pinfunction "3_3") (pintype "passive+no_connect"))
    )
    (net (code "224") (name "unconnected-(U7-Pad4)") (class "Default")
      (node (ref "U7") (pin "4") (pinfunction "4_4") (pintype "passive+no_connect"))
    )
    (net (code "225") (name "unconnected-(U7-Pad5)") (class "Default")
      (node (ref "U7") (pin "5") (pinfunction "5_5") (pintype "passive+no_connect"))
    )
    (net (code "226") (name "unconnected-(U7-Pad6)") (class "Default")
      (node (ref "U7") (pin "6") (pinfunction "6_6") (pintype "passive+no_connect"))
    )
    (net (code "227") (name "unconnected-(U7-Pad11)") (class "Default")
      (node (ref "U7") (pin "11") (pinfunction "11_11") (pintype "passive+no_connect"))
    )
    (net (code "228") (name "unconnected-(U7-Pad12)") (class "Default")
      (node (ref "U7") (pin "12") (pinfunction "12_12") (pintype "passive+no_connect"))
    )
    (net (code "229") (name "unconnected-(U7-Pad13)") (class "Default")
      (node (ref "U7") (pin "13") (pinfunction "13_13") (pintype "passive+no_connect"))
    )
    (net (code "230") (name "unconnected-(U7-Pad14)") (class "Default")
      (node (ref "U7") (pin "14") (pinfunction "14_14") (pintype "passive+no_connect"))
    )
    (net (code "231") (name "unconnected-(U8-Pad36)") (class "Default")
      (node (ref "U8") (pin "36") (pinfunction "36_36") (pintype "passive+no_connect"))
    )
    (net (code "232") (name "unconnected-(U8-Pad40)") (class "Default")
      (node (ref "U8") (pin "40") (pinfunction "40_40") (pintype "passive+no_connect"))
    )
    (net (code "233") (name "unconnected-(U8-Pad55)") (class "Default")
      (node (ref "U8") (pin "55") (pinfunction "55_55") (pintype "passive+no_connect"))
    )
    (net (code "234") (name "unconnected-(U8-Pad56)") (class "Default")
      (node (ref "U8") (pin "56") (pinfunction "56_56") (pintype "passive+no_connect"))
    )
    (net (code "235") (name "unconnected-(U8-Pad57)") (class "Default")
      (node (ref "U8") (pin "57") (pinfunction "57_57") (pintype "passive+no_connect"))
    )
    (net (code "236") (name "unconnected-(U8-Pad58)") (class "Default")
      (node (ref "U8") (pin "58") (pinfunction "58_58") (pintype "passive+no_connect"))
    )
    (net (code "237") (name "unconnected-(U8-Pad59)") (class "Default")
      (node (ref "U8") (pin "59") (pinfunction "59_59") (pintype "passive+no_connect"))
    )
    (net (code "238") (name "unconnected-(U8-Pad60)") (class "Default")
      (node (ref "U8") (pin "60") (pinfunction "60_60") (pintype "passive+no_connect"))
    )
    (net (code "239") (name "unconnected-(U12-Pad2)") (class "Default")
      (node (ref "U12") (pin "2") (pinfunction "2_2") (pintype "passive+no_connect"))
    )
  )
)
